# PX4FMUv1_7_1.net
KiCad netlist of a schematic drawn in EAGLE
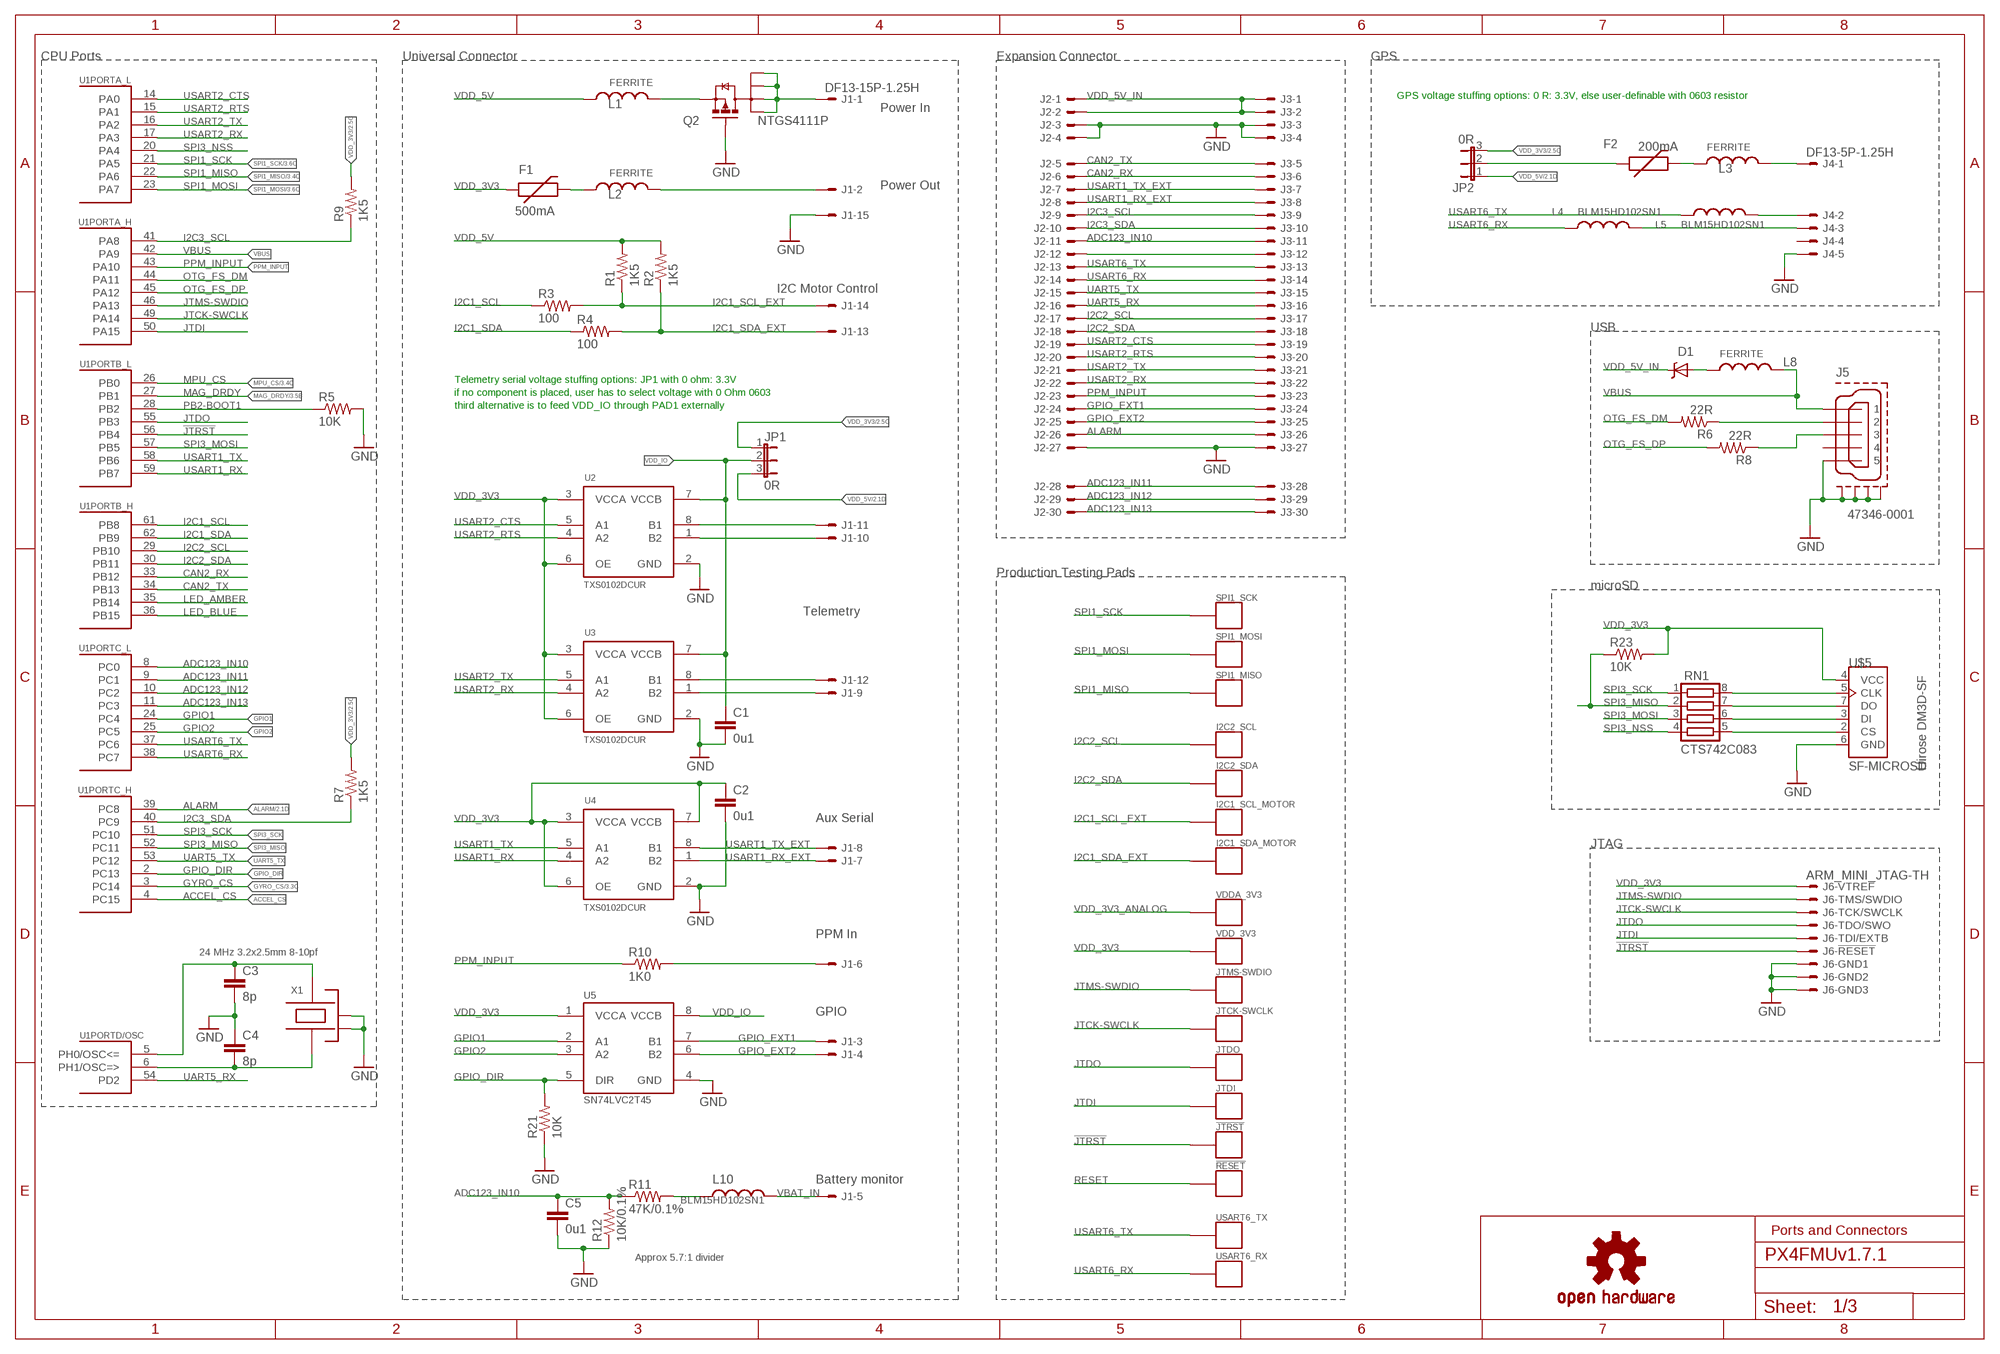
[diagram p0: schematic, sheet 1]
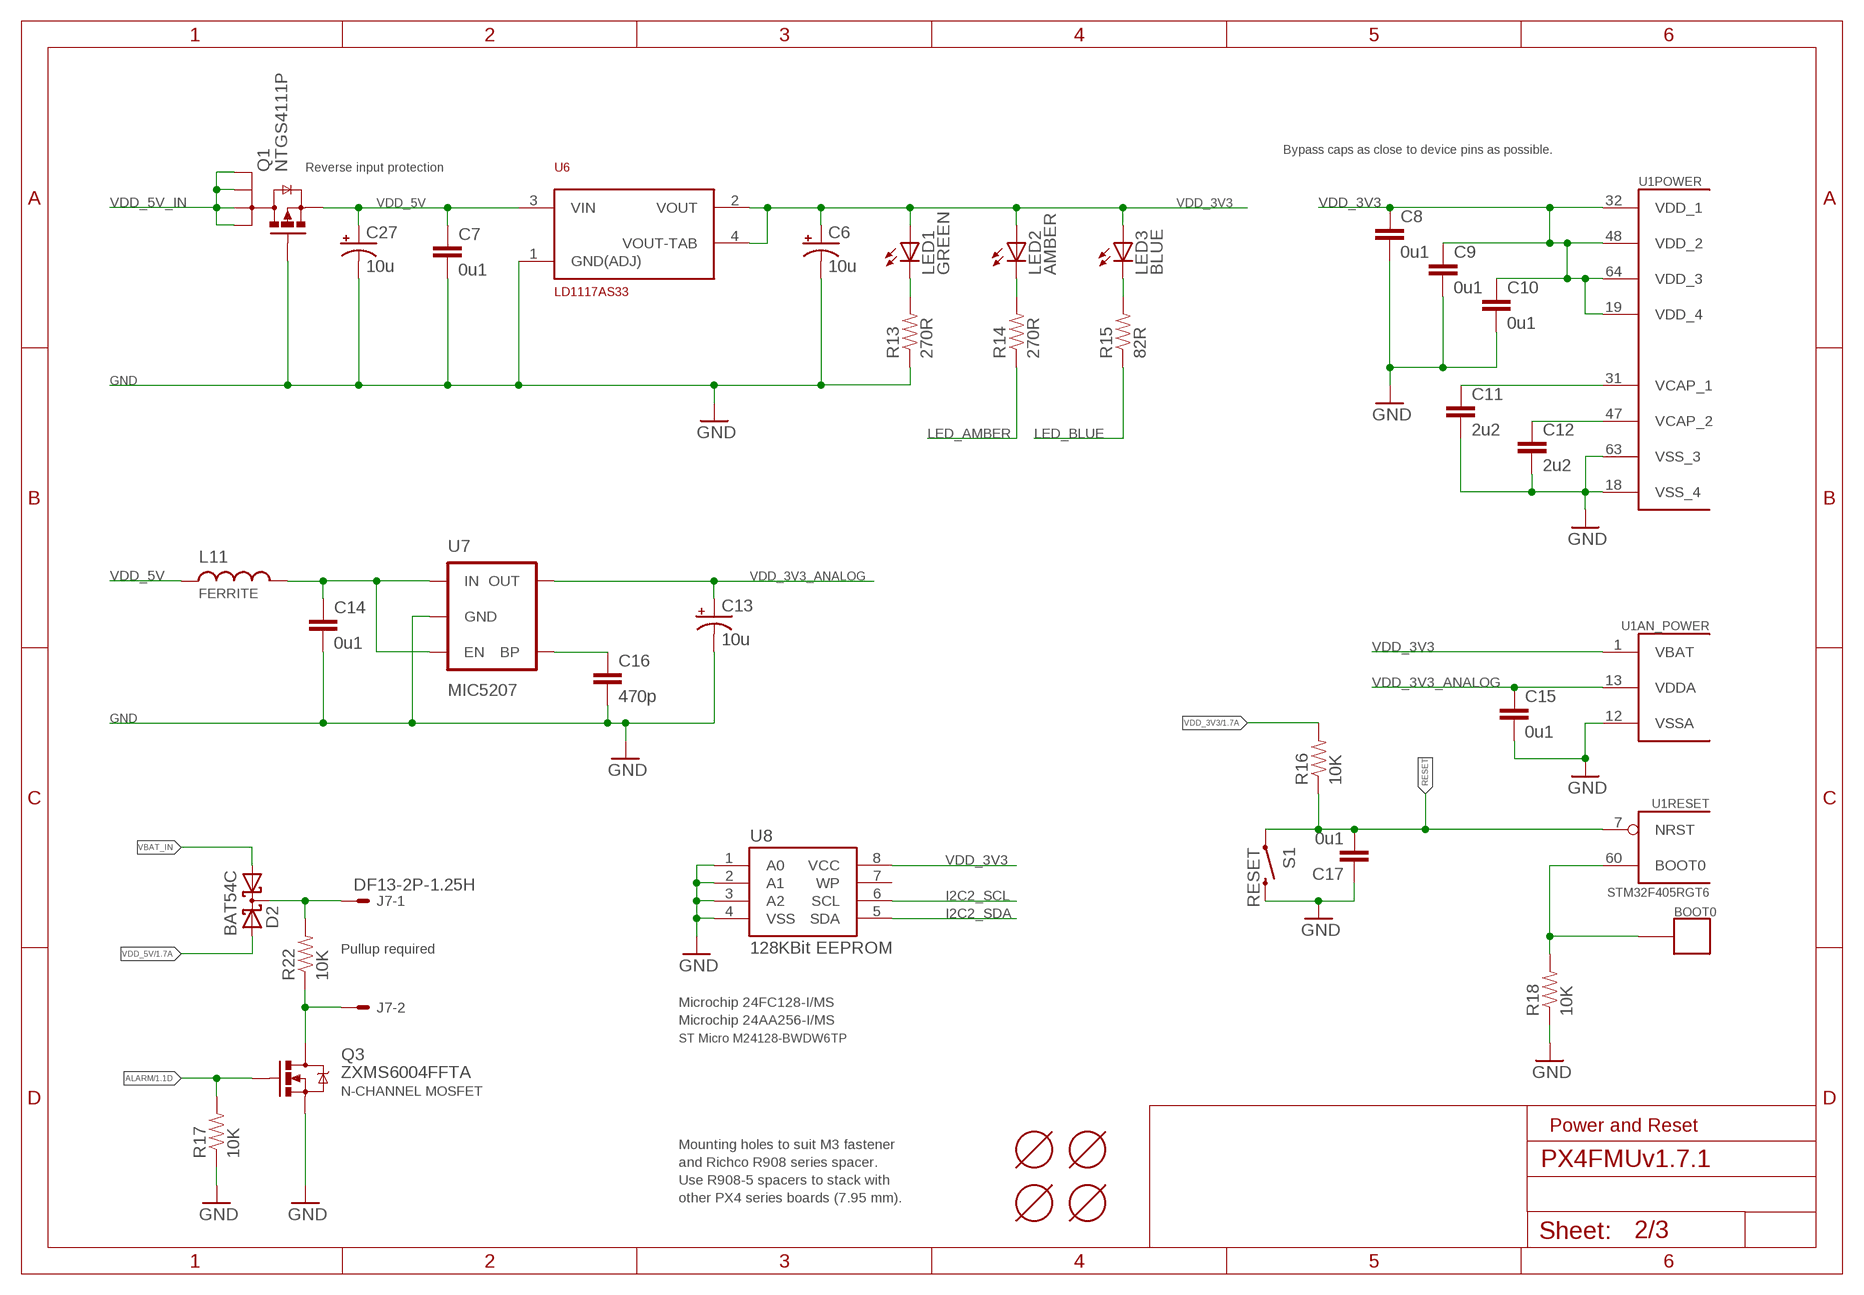
[diagram p1: schematic, sheet 2]
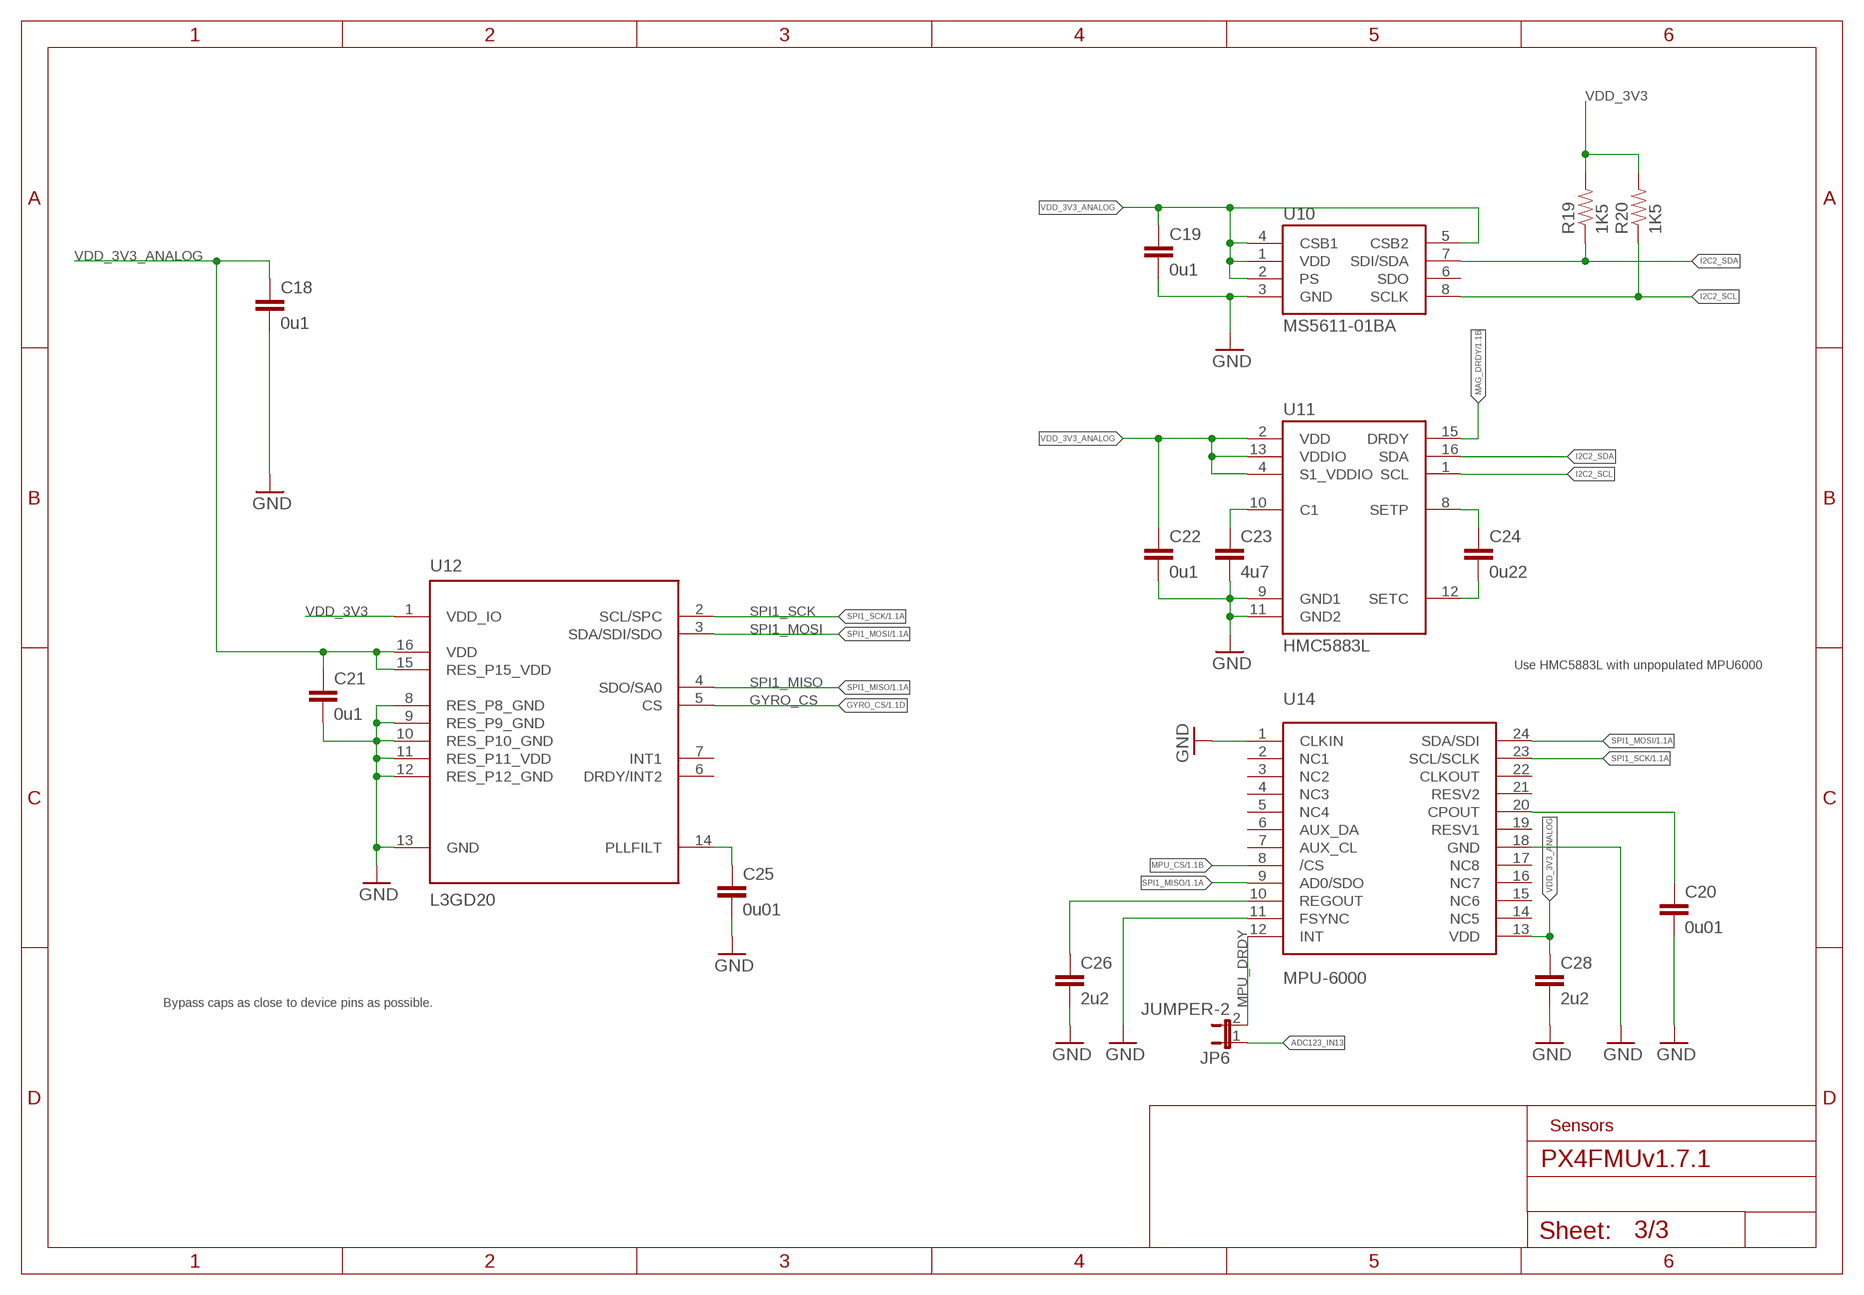
[diagram p2: schematic, sheet 3]

(export (version "E")
  (design (tool "Eeschema 10.0.6"))
  (components
    (comp (ref "BOOT0")
      (value "PAD.04")
      (footprint "eagle-import:PAD.04X.04")
      (libsource (lib "eagle-import") (part "PAD.04"))
    )
    (comp (ref "C6")
      (value "10u")
      (footprint "eagle-import:EIA3216")
      (fields (field (name "PARTNO") "F931A106MAA"))
      (libsource (lib "eagle-import") (part "CAP_POL1206"))
    )
    (comp (ref "C7")
      (value "0u1")
      (footprint "eagle-import:0402-CAP")
      (fields (field (name "PARTNO") "CC0402ZRY5V7BB104"))
      (libsource (lib "eagle-import") (part "CAP0402-CAP"))
    )
    (comp (ref "C8")
      (value "0u1")
      (footprint "eagle-import:0402-CAP")
      (fields (field (name "PARTNO") "CC0402ZRY5V7BB104"))
      (libsource (lib "eagle-import") (part "CAP0402-CAP"))
    )
    (comp (ref "C9")
      (value "0u1")
      (footprint "eagle-import:0402-CAP")
      (fields (field (name "PARTNO") "CC0402ZRY5V7BB104"))
      (libsource (lib "eagle-import") (part "CAP0402-CAP"))
    )
    (comp (ref "C10")
      (value "0u1")
      (footprint "eagle-import:0402-CAP")
      (fields (field (name "PARTNO") "CC0402ZRY5V7BB104"))
      (libsource (lib "eagle-import") (part "CAP0402-CAP"))
    )
    (comp (ref "C11")
      (value "2u2")
      (footprint "eagle-import:0402-CAP")
      (fields (field (name "PARTNO") "C1608Y5V1C225Z"))
      (libsource (lib "eagle-import") (part "CAP0402-CAP"))
    )
    (comp (ref "C12")
      (value "2u2")
      (footprint "eagle-import:0402-CAP")
      (fields (field (name "PARTNO") "C1608Y5V1C225Z"))
      (libsource (lib "eagle-import") (part "CAP0402-CAP"))
    )
    (comp (ref "C13")
      (value "10u")
      (footprint "eagle-import:EIA3216")
      (fields (field (name "PARTNO") "F931A106MAA"))
      (libsource (lib "eagle-import") (part "CAP_POL1206"))
    )
    (comp (ref "C14")
      (value "0u1")
      (footprint "eagle-import:0402-CAP")
      (fields (field (name "PARTNO") "CC0402ZRY5V7BB104"))
      (libsource (lib "eagle-import") (part "CAP0402-CAP"))
    )
    (comp (ref "C15")
      (value "0u1")
      (footprint "eagle-import:0402-CAP")
      (fields (field (name "PARTNO") "CC0402ZRY5V7BB104"))
      (libsource (lib "eagle-import") (part "CAP0402-CAP"))
    )
    (comp (ref "C16")
      (value "470p")
      (footprint "eagle-import:0402-CAP")
      (fields (field (name "PARTNO") "CC0402KRX7R9BB471"))
      (libsource (lib "eagle-import") (part "CAP0402-CAP"))
    )
    (comp (ref "C17")
      (value "0u1")
      (footprint "eagle-import:0402-CAP")
      (fields (field (name "PARTNO") "CC0402ZRY5V7BB104"))
      (libsource (lib "eagle-import") (part "CAP0402-CAP"))
    )
    (comp (ref "C27")
      (value "10u")
      (footprint "eagle-import:EIA3216")
      (fields (field (name "PARTNO") "F931A106MAA"))
      (libsource (lib "eagle-import") (part "CAP_POL1206"))
    )
    (comp (ref "D2")
      (value "BAT54C")
      (footprint "eagle-import:SOT23-3")
      (fields (field (name "PARTNO") "BAT54C-7-F"))
      (libsource (lib "eagle-import") (part "BAT54C"))
    )
    (comp (ref "J7")
      (value "DF13-2P-1.25H")
      (footprint "eagle-import:DF13A-2P-1.25H")
      (fields (field (name "PARTNO") "DF13-2P-1.25H(20)"))
      (libsource (lib "eagle-import") (part "DF13-2P-1.25?H"))
    )
    (comp (ref "L11")
      (value "FERRITE")
      (footprint "eagle-import:0402-IND")
      (fields (field (name "PARTNO") "BKP1005HS121-T"))
      (libsource (lib "eagle-import") (part "INDUCTOR0402"))
    )
    (comp (ref "LED1")
      (value "GREEN")
      (footprint "eagle-import:LED-0603")
      (fields (field (name "PARTNO") "LNJ337W83RA"))
      (libsource (lib "eagle-import") (part "LED0603"))
    )
    (comp (ref "LED2")
      (value "AMBER")
      (footprint "eagle-import:LED-0603")
      (fields (field (name "PARTNO") "LNJ437W84RA"))
      (libsource (lib "eagle-import") (part "LED0603"))
    )
    (comp (ref "LED3")
      (value "BLUE")
      (footprint "eagle-import:LED-0603")
      (fields (field (name "PARTNO") "LNJ937W8CRA"))
      (libsource (lib "eagle-import") (part "LED0603"))
    )
    (comp (ref "Q1")
      (value "NTGS4111P")
      (footprint "eagle-import:TSOP-6")
      (libsource (lib "eagle-import") (part "NTGS4111P"))
    )
    (comp (ref "Q3")
      (value "ZXMS6004FFTA")
      (footprint "eagle-import:SOT23-3")
      (libsource (lib "eagle-import") (part "MOSFET-NCHANNELSMD"))
    )
    (comp (ref "R13")
      (value "270R")
      (footprint "eagle-import:0402-RES")
      (fields (field (name "PARTNO") "RC0402JR-07270RL"))
      (libsource (lib "eagle-import") (part "RESISTOR0402-RES"))
    )
    (comp (ref "R14")
      (value "270R")
      (footprint "eagle-import:0402-RES")
      (fields (field (name "PARTNO") "RC0402JR-07270RL"))
      (libsource (lib "eagle-import") (part "RESISTOR0402-RES"))
    )
    (comp (ref "R15")
      (value "82R")
      (footprint "eagle-import:0402-RES")
      (fields (field (name "PARTNO") "RC0402JR-0782RL"))
      (libsource (lib "eagle-import") (part "RESISTOR0402-RES"))
    )
    (comp (ref "R16")
      (value "10K")
      (footprint "eagle-import:0402-RES")
      (fields (field (name "PARTNO") "RMCF0402FT10K0"))
      (libsource (lib "eagle-import") (part "RESISTOR0402-RES"))
    )
    (comp (ref "R17")
      (value "10K")
      (footprint "eagle-import:0402-RES")
      (fields (field (name "PARTNO") "RMCF0402FT10K0"))
      (libsource (lib "eagle-import") (part "RESISTOR0402-RES"))
    )
    (comp (ref "R18")
      (value "10K")
      (footprint "eagle-import:0402-RES")
      (fields (field (name "PARTNO") "RMCF0402FT10K0"))
      (libsource (lib "eagle-import") (part "RESISTOR0402-RES"))
    )
    (comp (ref "R22")
      (value "10K")
      (footprint "eagle-import:0402-RES")
      (fields (field (name "PARTNO") "RMCF0402FT10K0"))
      (libsource (lib "eagle-import") (part "RESISTOR0402-RES"))
    )
    (comp (ref "S1")
      (value "RESET")
      (footprint "eagle-import:EVQP7J01K")
      (fields (field (name "PARTNO") "EVQP7J01K"))
      (libsource (lib "eagle-import") (part "SWITCH-MOMENTARY-2"))
    )
    (comp (ref "U$1")
      (value "MOUNT-HOLE3.1MM")
      (footprint "eagle-import:MOUNT-HOLE3.1")
      (libsource (lib "eagle-import") (part "MOUNT-HOLE3.1MM"))
    )
    (comp (ref "U$2")
      (value "MOUNT-HOLE3.1MM")
      (footprint "eagle-import:MOUNT-HOLE3.1")
      (libsource (lib "eagle-import") (part "MOUNT-HOLE3.1MM"))
    )
    (comp (ref "U$3")
      (value "MOUNT-HOLE3.1MM")
      (footprint "eagle-import:MOUNT-HOLE3.1")
      (libsource (lib "eagle-import") (part "MOUNT-HOLE3.1MM"))
    )
    (comp (ref "U$4")
      (value "MOUNT-HOLE3.1MM")
      (footprint "eagle-import:MOUNT-HOLE3.1")
      (libsource (lib "eagle-import") (part "MOUNT-HOLE3.1MM"))
    )
    (comp (ref "U1")
      (value "STM32F405RGT6")
      (footprint "eagle-import:TQFP64")
      (fields (field (name "PARTNO") "STM32F405RGT6"))
      (libsource (lib "eagle-import") (part "STM32F20X_TQFP64"))
    )
    (comp (ref "U6")
      (value "LD1117AS33")
      (footprint "eagle-import:SOT-223")
      (libsource (lib "eagle-import") (part "LD1117AS33"))
    )
    (comp (ref "U7")
      (value "MIC5207")
      (footprint "eagle-import:SOT23-5")
      (fields (field (name "PARTNO") "MIC5207-3.3YM5"))
      (libsource (lib "eagle-import") (part "V_REG_LDOSMD"))
    )
    (comp (ref "U8")
      (value "128KBit EEPROM")
      (footprint "eagle-import:MSOP-8")
      (fields (field (name "PARTNO") "24FC128-I/MS"))
      (libsource (lib "eagle-import") (part "EEPROM-I2CMSOP"))
    )
    (comp (ref "C18")
      (value "0u1")
      (footprint "eagle-import:0402-CAP")
      (fields (field (name "PARTNO") "CC0402ZRY5V7BB104"))
      (libsource (lib "eagle-import") (part "CAP0402-CAP"))
    )
    (comp (ref "C19")
      (value "0u1")
      (footprint "eagle-import:0402-CAP")
      (fields (field (name "PARTNO") "CC0402ZRY5V7BB104"))
      (libsource (lib "eagle-import") (part "CAP0402-CAP"))
    )
    (comp (ref "C20")
      (value "0u01")
      (footprint "eagle-import:0402-CAP")
      (fields (field (name "PARTNO") "CC0402KRX7R7BB103"))
      (libsource (lib "eagle-import") (part "CAP0402-CAP"))
    )
    (comp (ref "C21")
      (value "0u1")
      (footprint "eagle-import:0402-CAP")
      (fields (field (name "PARTNO") "CC0402ZRY5V7BB104"))
      (libsource (lib "eagle-import") (part "CAP0402-CAP"))
    )
    (comp (ref "C22")
      (value "0u1")
      (footprint "eagle-import:0402-CAP")
      (fields (field (name "PARTNO") "CC0402ZRY5V7BB104"))
      (libsource (lib "eagle-import") (part "CAP0402-CAP"))
    )
    (comp (ref "C23")
      (value "4u7")
      (footprint "eagle-import:0402-CAP")
      (fields (field (name "PARTNO") "C1608Y5V0J475Z"))
      (libsource (lib "eagle-import") (part "CAP0402-CAP"))
    )
    (comp (ref "C24")
      (value "0u22")
      (footprint "eagle-import:0402-CAP")
      (fields (field (name "PARTNO") "C1005Y5V1C224Z"))
      (libsource (lib "eagle-import") (part "CAP0402-CAP"))
    )
    (comp (ref "C25")
      (value "0u01")
      (footprint "eagle-import:0402-CAP")
      (fields (field (name "PARTNO") "CC0402KRX7R7BB103"))
      (libsource (lib "eagle-import") (part "CAP0402-CAP"))
    )
    (comp (ref "C26")
      (value "2u2")
      (footprint "eagle-import:0402-CAP")
      (fields (field (name "PARTNO") "C1608Y5V1C225Z"))
      (libsource (lib "eagle-import") (part "CAP0402-CAP"))
    )
    (comp (ref "C28")
      (value "2u2")
      (footprint "eagle-import:0402-CAP")
      (fields (field (name "PARTNO") "C1608Y5V1C225Z"))
      (libsource (lib "eagle-import") (part "CAP0402-CAP"))
    )
    (comp (ref "JP6")
      (value "JUMPER-2")
      (footprint "eagle-import:SJ_2")
      (libsource (lib "eagle-import") (part "JUMPER-2"))
    )
    (comp (ref "R19")
      (value "1K5")
      (footprint "eagle-import:0402-RES")
      (fields (field (name "PARTNO") "RMCF0402JT1K50"))
      (libsource (lib "eagle-import") (part "RESISTOR0402-RES"))
    )
    (comp (ref "R20")
      (value "1K5")
      (footprint "eagle-import:0402-RES")
      (fields (field (name "PARTNO") "RMCF0402JT1K50"))
      (libsource (lib "eagle-import") (part "RESISTOR0402-RES"))
    )
    (comp (ref "U10")
      (value "MS5611-01BA")
      (footprint "eagle-import:MS5611-01BA")
      (libsource (lib "eagle-import") (part "MS5611-01BA"))
    )
    (comp (ref "U11")
      (value "HMC5883L")
      (footprint "eagle-import:HMC5883L-MAN")
      (libsource (lib "eagle-import") (part "HMC5883L"))
    )
    (comp (ref "U12")
      (value "L3GD20")
      (footprint "eagle-import:L3G4200DH-MAN")
      (libsource (lib "eagle-import") (part "L3G4200DH-LL"))
    )
    (comp (ref "U14")
      (value "MPU-6000")
      (footprint "eagle-import:QFN-24")
      (libsource (lib "eagle-import") (part "MPU-6000"))
    )
    (comp (ref "!JTRST")
      (value "PAD.04")
      (footprint "eagle-import:PAD.04X.04")
      (libsource (lib "eagle-import") (part "PAD.04"))
    )
    (comp (ref "!RESET")
      (value "PAD.04")
      (footprint "eagle-import:PAD.04X.04")
      (libsource (lib "eagle-import") (part "PAD.04"))
    )
    (comp (ref "C1")
      (value "0u1")
      (footprint "eagle-import:0402-CAP")
      (fields (field (name "PARTNO") "CC0402ZRY5V7BB104"))
      (libsource (lib "eagle-import") (part "CAP0402-CAP"))
    )
    (comp (ref "C2")
      (value "0u1")
      (footprint "eagle-import:0402-CAP")
      (fields (field (name "PARTNO") "CC0402ZRY5V7BB104"))
      (libsource (lib "eagle-import") (part "CAP0402-CAP"))
    )
    (comp (ref "C3")
      (value "8p")
      (footprint "eagle-import:0402-CAP")
      (fields (field (name "PARTNO") "C1005C0G1H080C"))
      (libsource (lib "eagle-import") (part "CAP0402-CAP"))
    )
    (comp (ref "C4")
      (value "8p")
      (footprint "eagle-import:0402-CAP")
      (fields (field (name "PARTNO") "C1005C0G1H080C"))
      (libsource (lib "eagle-import") (part "CAP0402-CAP"))
    )
    (comp (ref "C5")
      (value "0u1")
      (footprint "eagle-import:0402-CAP")
      (fields (field (name "PARTNO") "CC0402ZRY5V7BB104"))
      (libsource (lib "eagle-import") (part "CAP0402-CAP"))
    )
    (comp (ref "D1")
      (value "MSS1P4-M3")
      (footprint "eagle-import:MICROSMP")
      (fields (field (name "PARTNO") "MSS1P4-M3/89A"))
      (libsource (lib "eagle-import") (part "DIODE-SCHOTTKY_MSMP"))
    )
    (comp (ref "F1")
      (value "500mA")
      (footprint "eagle-import:0402-PTC")
      (fields (field (name "PARTNO") "MF-FSMF050X-2"))
      (libsource (lib "eagle-import") (part "PTC0402"))
    )
    (comp (ref "F2")
      (value "200mA")
      (footprint "eagle-import:0402-PTC")
      (fields (field (name "PARTNO") "MF-FSMF020X-2"))
      (libsource (lib "eagle-import") (part "PTC0402"))
    )
    (comp (ref "I2C1_SCL_MOTOR")
      (value "PAD.03")
      (footprint "eagle-import:PAD.03X.03")
      (libsource (lib "eagle-import") (part "PAD.03"))
    )
    (comp (ref "I2C1_SDA_MOTOR")
      (value "PAD.03")
      (footprint "eagle-import:PAD.03X.03")
      (libsource (lib "eagle-import") (part "PAD.03"))
    )
    (comp (ref "I2C2_SCL")
      (value "PAD.03")
      (footprint "eagle-import:PAD.03X.03")
      (libsource (lib "eagle-import") (part "PAD.03"))
    )
    (comp (ref "I2C2_SDA")
      (value "PAD.04")
      (footprint "eagle-import:PAD.04X.04")
      (libsource (lib "eagle-import") (part "PAD.04"))
    )
    (comp (ref "J1")
      (value "DF13-15P-1.25H")
      (footprint "eagle-import:DF13A-15P-1.25H")
      (fields (field (name "PARTNO") "DF13A-15P-1.25H(20)"))
      (libsource (lib "eagle-import") (part "DF13-15P-1.25?H"))
    )
    (comp (ref "J2")
      (value "HEADER_2X15-REV")
      (footprint "eagle-import:HEADER_2MM_2X15_REVERSE")
      (fields (field (name "BOM") "EXCLUDE") (field (name "PARTNO") "953230-2000-AR-PR"))
      (libsource (lib "eagle-import") (part "HEADER_2X15-REV"))
    )
    (comp (ref "J3")
      (value "HEADER_2X15")
      (footprint "eagle-import:HEADER_2MM_2X15")
      (fields (field (name "PARTNO") "953230-2000-AR-PR"))
      (libsource (lib "eagle-import") (part "HEADER_2X15-SMD"))
    )
    (comp (ref "J4")
      (value "DF13-5P-1.25H")
      (footprint "eagle-import:DF13A-5P-1.25H")
      (fields (field (name "PARTNO") "DF13A-5P-1.25H(20)"))
      (libsource (lib "eagle-import") (part "DF13-5P-1.25?H"))
    )
    (comp (ref "J5")
      (value "47346-0001")
      (footprint "eagle-import:MOLEX-47346-0001")
      (libsource (lib "eagle-import") (part "MOLEX-47346-0001"))
    )
    (comp (ref "J6")
      (value "ARM_MINI_JTAG-TH")
      (footprint "eagle-import:FTSH-105-01-XXX-DV")
      (fields (field (name "PARTNO") "M50-3900542"))
      (libsource (lib "eagle-import") (part "ARM_MINI_JTAG-TH"))
    )
    (comp (ref "JP1")
      (value "0R")
      (footprint "eagle-import:SJ_3_0603_PASTE1&2")
      (fields (field (name "PARTNO") "RMCF0402ZT0R00"))
      (libsource (lib "eagle-import") (part "JUMPER-30603"))
    )
    (comp (ref "JP2")
      (value "0R")
      (footprint "eagle-import:SJ_3_0603_PASTE1&2")
      (fields (field (name "PARTNO") "RMCF0402ZT0R00"))
      (libsource (lib "eagle-import") (part "JUMPER-30603"))
    )
    (comp (ref "JTCK-SWCLK")
      (value "PAD.04")
      (footprint "eagle-import:PAD.04X.04")
      (libsource (lib "eagle-import") (part "PAD.04"))
    )
    (comp (ref "JTDI")
      (value "PAD.04")
      (footprint "eagle-import:PAD.04X.04")
      (libsource (lib "eagle-import") (part "PAD.04"))
    )
    (comp (ref "JTDO")
      (value "PAD.04")
      (footprint "eagle-import:PAD.04X.04")
      (libsource (lib "eagle-import") (part "PAD.04"))
    )
    (comp (ref "JTMS-SWDIO")
      (value "PAD.04")
      (footprint "eagle-import:PAD.04X.04")
      (libsource (lib "eagle-import") (part "PAD.04"))
    )
    (comp (ref "L1")
      (value "FERRITE")
      (footprint "eagle-import:0402-IND")
      (fields (field (name "PARTNO") "BKP1005HS121-T"))
      (libsource (lib "eagle-import") (part "INDUCTOR0402"))
    )
    (comp (ref "L2")
      (value "FERRITE")
      (footprint "eagle-import:0402-IND")
      (fields (field (name "PARTNO") "BKP1005HS121-T"))
      (libsource (lib "eagle-import") (part "INDUCTOR0402"))
    )
    (comp (ref "L3")
      (value "FERRITE")
      (footprint "eagle-import:0402-IND")
      (fields (field (name "PARTNO") "BKP1005HS121-T"))
      (libsource (lib "eagle-import") (part "INDUCTOR0402"))
    )
    (comp (ref "L4")
      (value "BLM15HD102SN1")
      (footprint "eagle-import:0402-IND")
      (libsource (lib "eagle-import") (part "INDUCTOR0402"))
    )
    (comp (ref "L5")
      (value "BLM15HD102SN1")
      (footprint "eagle-import:0402-IND")
      (libsource (lib "eagle-import") (part "INDUCTOR0402"))
    )
    (comp (ref "L8")
      (value "FERRITE")
      (footprint "eagle-import:0402-IND")
      (fields (field (name "PARTNO") "BKP1005HS121-T"))
      (libsource (lib "eagle-import") (part "INDUCTOR0402"))
    )
    (comp (ref "L10")
      (value "BLM15HD102SN1")
      (footprint "eagle-import:0402-IND")
      (libsource (lib "eagle-import") (part "INDUCTOR0402"))
    )
    (comp (ref "Q2")
      (value "NTGS4111P")
      (footprint "eagle-import:TSOP-6")
      (libsource (lib "eagle-import") (part "NTGS4111P"))
    )
    (comp (ref "R1")
      (value "1K5")
      (footprint "eagle-import:0402-RES")
      (fields (field (name "PARTNO") "RMCF0402JT1K50"))
      (libsource (lib "eagle-import") (part "RESISTOR0402-RES"))
    )
    (comp (ref "R2")
      (value "1K5")
      (footprint "eagle-import:0402-RES")
      (fields (field (name "PARTNO") "RMCF0402JT1K50"))
      (libsource (lib "eagle-import") (part "RESISTOR0402-RES"))
    )
    (comp (ref "R3")
      (value "100")
      (footprint "eagle-import:0402-RES")
      (fields (field (name "PARTNO") "RMCF0402JT100R"))
      (libsource (lib "eagle-import") (part "RESISTOR0402-RES"))
    )
    (comp (ref "R4")
      (value "100")
      (footprint "eagle-import:0402-RES")
      (fields (field (name "PARTNO") "RMCF0402JT100R"))
      (libsource (lib "eagle-import") (part "RESISTOR0402-RES"))
    )
    (comp (ref "R5")
      (value "10K")
      (footprint "eagle-import:0402-RES")
      (fields (field (name "PARTNO") "RMCF0402FT10K0"))
      (libsource (lib "eagle-import") (part "RESISTOR0402-RES"))
    )
    (comp (ref "R6")
      (value "22R")
      (footprint "eagle-import:0402-RES")
      (fields (field (name "PARTNO") "RMCF0402JT22R0"))
      (libsource (lib "eagle-import") (part "RESISTOR0402-RES"))
    )
    (comp (ref "R7")
      (value "1K5")
      (footprint "eagle-import:0402-RES")
      (fields (field (name "PARTNO") "RMCF0402JT1K50"))
      (libsource (lib "eagle-import") (part "RESISTOR0402-RES"))
    )
    (comp (ref "R8")
      (value "22R")
      (footprint "eagle-import:0402-RES")
      (fields (field (name "PARTNO") "RMCF0402JT22R0"))
      (libsource (lib "eagle-import") (part "RESISTOR0402-RES"))
    )
    (comp (ref "R9")
      (value "1K5")
      (footprint "eagle-import:0402-RES")
      (fields (field (name "PARTNO") "RMCF0402JT1K50"))
      (libsource (lib "eagle-import") (part "RESISTOR0402-RES"))
    )
    (comp (ref "R10")
      (value "1K0")
      (footprint "eagle-import:0402-RES")
      (fields (field (name "PARTNO") "RMCF0402JT1K00"))
      (libsource (lib "eagle-import") (part "RESISTOR0402-RES"))
    )
    (comp (ref "R11")
      (value "47K/0.1%")
      (footprint "eagle-import:0402-RES")
      (fields (field (name "PARTNO") "ERA-2AEB473X"))
      (libsource (lib "eagle-import") (part "RESISTOR0402-RES"))
    )
    (comp (ref "R12")
      (value "10K/0.1%")
      (footprint "eagle-import:0402-RES")
      (fields (field (name "PARTNO") "ERA-2AEB103X"))
      (libsource (lib "eagle-import") (part "RESISTOR0402-RES"))
    )
    (comp (ref "R21")
      (value "10K")
      (footprint "eagle-import:0402-RES")
      (fields (field (name "PARTNO") "RMCF0402FT10K0"))
      (libsource (lib "eagle-import") (part "RESISTOR0402-RES"))
    )
    (comp (ref "R23")
      (value "10K")
      (footprint "eagle-import:0402-RES")
      (fields (field (name "PARTNO") "RMCF0402FT10K0"))
      (libsource (lib "eagle-import") (part "RESISTOR0402-RES"))
    )
    (comp (ref "RN1")
      (value "CTS742C083")
      (footprint "eagle-import:CTS742C083")
      (fields (field (name "PARTNO") "TC164-JR-07100RL"))
      (libsource (lib "eagle-import") (part "CTS742C083"))
    )
    (comp (ref "SPI1_MISO")
      (value "PAD.04")
      (footprint "eagle-import:PAD.04X.04")
      (libsource (lib "eagle-import") (part "PAD.04"))
    )
    (comp (ref "SPI1_MOSI")
      (value "PAD.04")
      (footprint "eagle-import:PAD.04X.04")
      (libsource (lib "eagle-import") (part "PAD.04"))
    )
    (comp (ref "SPI1_SCK")
      (value "PAD.04")
      (footprint "eagle-import:PAD.04X.04")
      (libsource (lib "eagle-import") (part "PAD.04"))
    )
    (comp (ref "U$5")
      (value "SF-MICROSD")
      (footprint "eagle-import:MICROSD")
      (libsource (lib "eagle-import") (part "SF-MICROSD"))
    )
    (comp (ref "U$7")
      (value "OSHW-LOGOS")
      (footprint "eagle-import:OSHW-LOGO-S")
      (libsource (lib "eagle-import") (part "OSHW-LOGOS"))
    )
    (comp (ref "U2")
      (value "TXS0102DCUR")
      (footprint "eagle-import:TI-DCU")
      (libsource (lib "eagle-import") (part "TXS0102DCUR"))
    )
    (comp (ref "U3")
      (value "TXS0102DCUR")
      (footprint "eagle-import:TI-DCU")
      (libsource (lib "eagle-import") (part "TXS0102DCUR"))
    )
    (comp (ref "U4")
      (value "TXS0102DCUR")
      (footprint "eagle-import:TI-DCU")
      (libsource (lib "eagle-import") (part "TXS0102DCUR"))
    )
    (comp (ref "U5")
      (value "SN74LVC2T45")
      (footprint "eagle-import:TI-DCU")
      (libsource (lib "eagle-import") (part "SN74LVC2T45DCUR"))
    )
    (comp (ref "USART6_RX")
      (value "PAD.04")
      (footprint "eagle-import:PAD.04X.04")
      (libsource (lib "eagle-import") (part "PAD.04"))
    )
    (comp (ref "USART6_TX")
      (value "PAD.04")
      (footprint "eagle-import:PAD.04X.04")
      (libsource (lib "eagle-import") (part "PAD.04"))
    )
    (comp (ref "VDDA_3V3")
      (value "PAD.04")
      (footprint "eagle-import:PAD.04X.04")
      (libsource (lib "eagle-import") (part "PAD.04"))
    )
    (comp (ref "VDD_3V3")
      (value "PAD.04")
      (footprint "eagle-import:PAD.04X.04")
      (libsource (lib "eagle-import") (part "PAD.04"))
    )
    (comp (ref "X1")
      (value "24 MHz 3.2x2.5mm 8-10pf")
      (footprint "eagle-import:OSCILLATOR-3.2X2.5")
      (fields (field (name "PARTNO") "NX3225SA-24.000000MHZ"))
      (libsource (lib "eagle-import") (part "OSCILLATOR-3.2X2.5"))
    )
  )
  (nets
    (net (code "1") (name "ACCEL_CS") (class "Default")
      (node (ref "U1") (pin "4") (pinfunction "PC15_4") (pintype "bidirectional"))
    )
    (net (code "2") (name "ADC123_IN10") (class "Default")
      (node (ref "C5") (pin "1") (pinfunction "1_1") (pintype "passive"))
      (node (ref "J2") (pin "11") (pinfunction "S_11") (pintype "passive"))
      (node (ref "J3") (pin "11") (pinfunction "S_11") (pintype "passive"))
      (node (ref "R11") (pin "1") (pinfunction "1_1") (pintype "passive"))
      (node (ref "R12") (pin "2") (pinfunction "2_2") (pintype "passive"))
      (node (ref "U1") (pin "8") (pinfunction "PC0_8") (pintype "bidirectional"))
    )
    (net (code "3") (name "ADC123_IN11") (class "Default")
      (node (ref "J2") (pin "28") (pinfunction "S_28") (pintype "passive"))
      (node (ref "J3") (pin "28") (pinfunction "S_28") (pintype "passive"))
      (node (ref "U1") (pin "9") (pinfunction "PC1_9") (pintype "bidirectional"))
    )
    (net (code "4") (name "ADC123_IN12") (class "Default")
      (node (ref "J2") (pin "29") (pinfunction "S_29") (pintype "passive"))
      (node (ref "J3") (pin "29") (pinfunction "S_29") (pintype "passive"))
      (node (ref "U1") (pin "10") (pinfunction "PC2_10") (pintype "bidirectional"))
    )
    (net (code "5") (name "ADC123_IN13") (class "Default")
      (node (ref "J2") (pin "30") (pinfunction "S_30") (pintype "passive"))
      (node (ref "J3") (pin "30") (pinfunction "S_30") (pintype "passive"))
      (node (ref "JP6") (pin "1") (pinfunction "1_1") (pintype "passive"))
      (node (ref "U1") (pin "11") (pinfunction "PC3_11") (pintype "bidirectional"))
    )
    (net (code "6") (name "ALARM") (class "Default")
      (node (ref "J2") (pin "26") (pinfunction "S_26") (pintype "passive"))
      (node (ref "J3") (pin "26") (pinfunction "S_26") (pintype "passive"))
      (node (ref "Q3") (pin "1") (pinfunction "G_1") (pintype "passive"))
      (node (ref "R17") (pin "2") (pinfunction "2_2") (pintype "passive"))
      (node (ref "U1") (pin "39") (pinfunction "PC8_39") (pintype "bidirectional"))
    )
    (net (code "7") (name "CAN2_RX") (class "Default")
      (node (ref "J2") (pin "6") (pinfunction "S_6") (pintype "passive"))
      (node (ref "J3") (pin "6") (pinfunction "S_6") (pintype "passive"))
      (node (ref "U1") (pin "33") (pinfunction "PB12_33") (pintype "bidirectional"))
    )
    (net (code "8") (name "CAN2_TX") (class "Default")
      (node (ref "J2") (pin "5") (pinfunction "S_5") (pintype "passive"))
      (node (ref "J3") (pin "5") (pinfunction "S_5") (pintype "passive"))
      (node (ref "U1") (pin "34") (pinfunction "PB13_34") (pintype "bidirectional"))
    )
    (net (code "9") (name "GND") (class "Default")
      (node (ref "C1") (pin "2") (pinfunction "2_2") (pintype "passive"))
      (node (ref "C10") (pin "2") (pinfunction "2_2") (pintype "passive"))
      (node (ref "C11") (pin "2") (pinfunction "2_2") (pintype "passive"))
      (node (ref "C12") (pin "2") (pinfunction "2_2") (pintype "passive"))
      (node (ref "C13") (pin "C") (pinfunction "-_C") (pintype "passive"))
      (node (ref "C14") (pin "2") (pinfunction "2_2") (pintype "passive"))
      (node (ref "C15") (pin "2") (pinfunction "2_2") (pintype "passive"))
      (node (ref "C16") (pin "2") (pinfunction "2_2") (pintype "passive"))
      (node (ref "C17") (pin "1") (pinfunction "1_1") (pintype "passive"))
      (node (ref "C18") (pin "2") (pinfunction "2_2") (pintype "passive"))
      (node (ref "C19") (pin "2") (pinfunction "2_2") (pintype "passive"))
      (node (ref "C2") (pin "2") (pinfunction "2_2") (pintype "passive"))
      (node (ref "C20") (pin "2") (pinfunction "2_2") (pintype "passive"))
      (node (ref "C21") (pin "2") (pinfunction "2_2") (pintype "passive"))
      (node (ref "C22") (pin "2") (pinfunction "2_2") (pintype "passive"))
      (node (ref "C23") (pin "2") (pinfunction "2_2") (pintype "passive"))
      (node (ref "C25") (pin "2") (pinfunction "2_2") (pintype "passive"))
      (node (ref "C26") (pin "2") (pinfunction "2_2") (pintype "passive"))
      (node (ref "C27") (pin "C") (pinfunction "-_C") (pintype "passive"))
      (node (ref "C28") (pin "2") (pinfunction "2_2") (pintype "passive"))
      (node (ref "C3") (pin "2") (pinfunction "2_2") (pintype "passive"))
      (node (ref "C4") (pin "1") (pinfunction "1_1") (pintype "passive"))
      (node (ref "C5") (pin "2") (pinfunction "2_2") (pintype "passive"))
      (node (ref "C6") (pin "C") (pinfunction "-_C") (pintype "passive"))
      (node (ref "C7") (pin "2") (pinfunction "2_2") (pintype "passive"))
      (node (ref "C8") (pin "2") (pinfunction "2_2") (pintype "passive"))
      (node (ref "C9") (pin "2") (pinfunction "2_2") (pintype "passive"))
      (node (ref "J1") (pin "15") (pinfunction "S_15") (pintype "passive"))
      (node (ref "J2") (pin "27") (pinfunction "S_27") (pintype "passive"))
      (node (ref "J2") (pin "3") (pinfunction "S_3") (pintype "passive"))
      (node (ref "J2") (pin "4") (pinfunction "S_4") (pintype "passive"))
      (node (ref "J3") (pin "27") (pinfunction "S_27") (pintype "passive"))
      (node (ref "J3") (pin "3") (pinfunction "S_3") (pintype "passive"))
      (node (ref "J3") (pin "4") (pinfunction "S_4") (pintype "passive"))
      (node (ref "J4") (pin "5") (pinfunction "S_5") (pintype "passive"))
      (node (ref "J5") (pin "GND") (pinfunction "5_GND") (pintype "power_in"))
      (node (ref "J5") (pin "GND1") (pinfunction "GND1_GND1") (pintype "bidirectional"))
      (node (ref "J5") (pin "GND2") (pinfunction "GND2_GND2") (pintype "bidirectional"))
      (node (ref "J5") (pin "GND3") (pinfunction "GND3_GND3") (pintype "bidirectional"))
      (node (ref "J5") (pin "GND4") (pinfunction "GND4_GND4") (pintype "bidirectional"))
      (node (ref "J6") (pin "3") (pinfunction "S_3") (pintype "passive"))
      (node (ref "J6") (pin "5") (pinfunction "S_5") (pintype "passive"))
      (node (ref "J6") (pin "9") (pinfunction "S_9") (pintype "passive"))
      (node (ref "Q1") (pin "3") (pinfunction "G_3") (pintype "passive"))
      (node (ref "Q2") (pin "3") (pinfunction "G_3") (pintype "passive"))
      (node (ref "Q3") (pin "2") (pinfunction "S_2") (pintype "passive"))
      (node (ref "R12") (pin "1") (pinfunction "1_1") (pintype "passive"))
      (node (ref "R13") (pin "1") (pinfunction "1_1") (pintype "passive"))
      (node (ref "R17") (pin "1") (pinfunction "1_1") (pintype "passive"))
      (node (ref "R18") (pin "1") (pinfunction "1_1") (pintype "passive"))
      (node (ref "R21") (pin "1") (pinfunction "1_1") (pintype "passive"))
      (node (ref "R5") (pin "2") (pinfunction "2_2") (pintype "passive"))
      (node (ref "S1") (pin "B3") (pinfunction "2_B3") (pintype "passive"))
      (node (ref "U$5") (pin "6") (pinfunction "GND_6") (pintype "power_in"))
      (node (ref "U1") (pin "12") (pinfunction "VSSA_12") (pintype "power_in"))
      (node (ref "U1") (pin "18") (pinfunction "VSS_4_18") (pintype "power_in"))
      (node (ref "U1") (pin "63") (pinfunction "VSS_3_63") (pintype "power_in"))
      (node (ref "U10") (pin "3") (pinfunction "GND_3") (pintype "bidirectional"))
      (node (ref "U11") (pin "11") (pinfunction "GND2_11") (pintype "bidirectional"))
      (node (ref "U11") (pin "9") (pinfunction "GND1_9") (pintype "bidirectional"))
      (node (ref "U12") (pin "10") (pinfunction "RES_P10_GND_10") (pintype "bidirectional"))
      (node (ref "U12") (pin "11") (pinfunction "RES_P11_VDD_11") (pintype "bidirectional"))
      (node (ref "U12") (pin "12") (pinfunction "RES_P12_GND_12") (pintype "bidirectional"))
      (node (ref "U12") (pin "13") (pinfunction "GND_13") (pintype "bidirectional"))
      (node (ref "U12") (pin "8") (pinfunction "RES_P8_GND_8") (pintype "bidirectional"))
      (node (ref "U12") (pin "9") (pinfunction "RES_P9_GND_9") (pintype "bidirectional"))
      (node (ref "U14") (pin "1") (pinfunction "CLKIN_1") (pintype "bidirectional"))
      (node (ref "U14") (pin "11") (pinfunction "FSYNC_11") (pintype "bidirectional"))
      (node (ref "U14") (pin "18") (pinfunction "GND_18") (pintype "bidirectional"))
      (node (ref "U2") (pin "2") (pinfunction "GND_2") (pintype "power_in"))
      (node (ref "U3") (pin "2") (pinfunction "GND_2") (pintype "power_in"))
      (node (ref "U4") (pin "2") (pinfunction "GND_2") (pintype "power_in"))
      (node (ref "U5") (pin "4") (pinfunction "GND_4") (pintype "power_in"))
      (node (ref "U6") (pin "1") (pinfunction "GND(ADJ)_1") (pintype "bidirectional"))
      (node (ref "U7") (pin "2") (pinfunction "GND_2") (pintype "input"))
      (node (ref "U8") (pin "1") (pinfunction "A0_1") (pintype "bidirectional"))
      (node (ref "U8") (pin "2") (pinfunction "A1_2") (pintype "bidirectional"))
      (node (ref "U8") (pin "3") (pinfunction "A2_3") (pintype "bidirectional"))
      (node (ref "U8") (pin "4") (pinfunction "VSS_4") (pintype "power_in"))
      (node (ref "X1") (pin "2") (pinfunction "NC_2_2") (pintype "power_in"))
      (node (ref "X1") (pin "4") (pinfunction "NC_4_4") (pintype "power_in"))
    )
    (net (code "10") (name "GPIO1") (class "Default")
      (node (ref "U1") (pin "24") (pinfunction "PC4_24") (pintype "bidirectional"))
      (node (ref "U5") (pin "2") (pinfunction "A1_2") (pintype "bidirectional"))
    )
    (net (code "11") (name "GPIO2") (class "Default")
      (node (ref "U1") (pin "25") (pinfunction "PC5_25") (pintype "bidirectional"))
      (node (ref "U5") (pin "3") (pinfunction "A2_3") (pintype "bidirectional"))
    )
    (net (code "12") (name "GPIO_DIR") (class "Default")
      (node (ref "R21") (pin "2") (pinfunction "2_2") (pintype "passive"))
      (node (ref "U1") (pin "2") (pinfunction "PC13_2") (pintype "bidirectional"))
      (node (ref "U5") (pin "5") (pinfunction "DIR_5") (pintype "input"))
    )
    (net (code "13") (name "GPIO_EXT1") (class "Default")
      (node (ref "J1") (pin "3") (pinfunction "S_3") (pintype "passive"))
      (node (ref "J2") (pin "24") (pinfunction "S_24") (pintype "passive"))
      (node (ref "J3") (pin "24") (pinfunction "S_24") (pintype "passive"))
      (node (ref "U5") (pin "7") (pinfunction "B1_7") (pintype "bidirectional"))
    )
    (net (code "14") (name "GPIO_EXT2") (class "Default")
      (node (ref "J1") (pin "4") (pinfunction "S_4") (pintype "passive"))
      (node (ref "J2") (pin "25") (pinfunction "S_25") (pintype "passive"))
      (node (ref "J3") (pin "25") (pinfunction "S_25") (pintype "passive"))
      (node (ref "U5") (pin "6") (pinfunction "B2_6") (pintype "bidirectional"))
    )
    (net (code "15") (name "GYRO_CS") (class "Default")
      (node (ref "U1") (pin "3") (pinfunction "PC14_3") (pintype "bidirectional"))
      (node (ref "U12") (pin "5") (pinfunction "CS_5") (pintype "input"))
    )
    (net (code "16") (name "I2C1_SCL") (class "Default")
      (node (ref "R3") (pin "1") (pinfunction "1_1") (pintype "passive"))
      (node (ref "U1") (pin "61") (pinfunction "PB8_61") (pintype "bidirectional"))
    )
    (net (code "17") (name "I2C1_SCL_EXT") (class "Default")
      (node (ref "I2C1_SCL_MOTOR") (pin "P$1") (pinfunction "P$1_P$1") (pintype "passive"))
      (node (ref "J1") (pin "14") (pinfunction "S_14") (pintype "passive"))
      (node (ref "R1") (pin "1") (pinfunction "1_1") (pintype "passive"))
      (node (ref "R3") (pin "2") (pinfunction "2_2") (pintype "passive"))
    )
    (net (code "18") (name "I2C1_SDA") (class "Default")
      (node (ref "R4") (pin "1") (pinfunction "1_1") (pintype "passive"))
      (node (ref "U1") (pin "62") (pinfunction "PB9_62") (pintype "bidirectional"))
    )
    (net (code "19") (name "I2C1_SDA_EXT") (class "Default")
      (node (ref "I2C1_SDA_MOTOR") (pin "P$1") (pinfunction "P$1_P$1") (pintype "passive"))
      (node (ref "J1") (pin "13") (pinfunction "S_13") (pintype "passive"))
      (node (ref "R2") (pin "1") (pinfunction "1_1") (pintype "passive"))
      (node (ref "R4") (pin "2") (pinfunction "2_2") (pintype "passive"))
    )
    (net (code "20") (name "I2C2_SCL") (class "Default")
      (node (ref "I2C2_SCL") (pin "P$1") (pinfunction "P$1_P$1") (pintype "passive"))
      (node (ref "J2") (pin "17") (pinfunction "S_17") (pintype "passive"))
      (node (ref "J3") (pin "17") (pinfunction "S_17") (pintype "passive"))
      (node (ref "R20") (pin "1") (pinfunction "1_1") (pintype "passive"))
      (node (ref "U1") (pin "29") (pinfunction "PB10_29") (pintype "bidirectional"))
      (node (ref "U10") (pin "8") (pinfunction "SCLK_8") (pintype "bidirectional"))
      (node (ref "U11") (pin "1") (pinfunction "SCL_1") (pintype "bidirectional"))
      (node (ref "U8") (pin "6") (pinfunction "SCL_6") (pintype "bidirectional"))
    )
    (net (code "21") (name "I2C2_SDA") (class "Default")
      (node (ref "I2C2_SDA") (pin "P$1") (pinfunction "P$1_P$1") (pintype "passive"))
      (node (ref "J2") (pin "18") (pinfunction "S_18") (pintype "passive"))
      (node (ref "J3") (pin "18") (pinfunction "S_18") (pintype "passive"))
      (node (ref "R19") (pin "1") (pinfunction "1_1") (pintype "passive"))
      (node (ref "U1") (pin "30") (pinfunction "PB11_30") (pintype "bidirectional"))
      (node (ref "U10") (pin "7") (pinfunction "SDI/SDA_7") (pintype "bidirectional"))
      (node (ref "U11") (pin "16") (pinfunction "SDA_16") (pintype "bidirectional"))
      (node (ref "U8") (pin "5") (pinfunction "SDA_5") (pintype "bidirectional"))
    )
    (net (code "22") (name "I2C3_SCL") (class "Default")
      (node (ref "J2") (pin "9") (pinfunction "S_9") (pintype "passive"))
      (node (ref "J3") (pin "9") (pinfunction "S_9") (pintype "passive"))
      (node (ref "R9") (pin "1") (pinfunction "1_1") (pintype "passive"))
      (node (ref "U1") (pin "41") (pinfunction "PA8_41") (pintype "bidirectional"))
    )
    (net (code "23") (name "I2C3_SDA") (class "Default")
      (node (ref "J2") (pin "10") (pinfunction "S_10") (pintype "passive"))
      (node (ref "J3") (pin "10") (pinfunction "S_10") (pintype "passive"))
      (node (ref "R7") (pin "1") (pinfunction "1_1") (pintype "passive"))
      (node (ref "U1") (pin "40") (pinfunction "PC9_40") (pintype "bidirectional"))
    )
    (net (code "24") (name "JTCK-SWCLK") (class "Default")
      (node (ref "J6") (pin "4") (pinfunction "S_4") (pintype "passive"))
      (node (ref "JTCK-SWCLK") (pin "P$1") (pinfunction "P$1_P$1") (pintype "passive"))
      (node (ref "U1") (pin "49") (pinfunction "PA14_49") (pintype "bidirectional"))
    )
    (net (code "25") (name "JTDI") (class "Default")
      (node (ref "J6") (pin "8") (pinfunction "S_8") (pintype "passive"))
      (node (ref "JTDI") (pin "P$1") (pinfunction "P$1_P$1") (pintype "passive"))
      (node (ref "U1") (pin "50") (pinfunction "PA15_50") (pintype "bidirectional"))
    )
    (net (code "26") (name "JTDO") (class "Default")
      (node (ref "J6") (pin "6") (pinfunction "S_6") (pintype "passive"))
      (node (ref "JTDO") (pin "P$1") (pinfunction "P$1_P$1") (pintype "passive"))
      (node (ref "U1") (pin "55") (pinfunction "PB3_55") (pintype "bidirectional"))
    )
    (net (code "27") (name "JTMS-SWDIO") (class "Default")
      (node (ref "J6") (pin "2") (pinfunction "S_2") (pintype "passive"))
      (node (ref "JTMS-SWDIO") (pin "P$1") (pinfunction "P$1_P$1") (pintype "passive"))
      (node (ref "U1") (pin "46") (pinfunction "PA13_46") (pintype "bidirectional"))
    )
    (net (code "28") (name "LED_AMBER") (class "Default")
      (node (ref "R14") (pin "1") (pinfunction "1_1") (pintype "passive"))
      (node (ref "U1") (pin "35") (pinfunction "PB14_35") (pintype "bidirectional"))
    )
    (net (code "29") (name "LED_BLUE") (class "Default")
      (node (ref "R15") (pin "1") (pinfunction "1_1") (pintype "passive"))
      (node (ref "U1") (pin "36") (pinfunction "PB15_36") (pintype "bidirectional"))
    )
    (net (code "30") (name "MAG_DRDY") (class "Default")
      (node (ref "U1") (pin "27") (pinfunction "PB1_27") (pintype "bidirectional"))
      (node (ref "U11") (pin "15") (pinfunction "DRDY_15") (pintype "bidirectional"))
    )
    (net (code "31") (name "MPU_CS") (class "Default")
      (node (ref "U1") (pin "26") (pinfunction "PB0_26") (pintype "bidirectional"))
      (node (ref "U14") (pin "8") (pinfunction "/CS_8") (pintype "bidirectional"))
    )
    (net (code "32") (name "Net-(D1-A)") (class "Default")
      (node (ref "D1") (pin "ANODE") (pinfunction "A_ANODE") (pintype "passive"))
      (node (ref "L8") (pin "1") (pinfunction "1_1") (pintype "passive"))
    )
    (net (code "33") (name "Net-(D2-CC)") (class "Default")
      (node (ref "D2") (pin "3") (pinfunction "CC_3") (pintype "passive"))
      (node (ref "J7") (pin "1") (pinfunction "S_1") (pintype "passive"))
      (node (ref "R22") (pin "2") (pinfunction "2_2") (pintype "passive"))
    )
    (net (code "34") (name "Net-(F1-Pad2)") (class "Default")
      (node (ref "F1") (pin "2") (pinfunction "2_2") (pintype "bidirectional"))
      (node (ref "L2") (pin "1") (pinfunction "1_1") (pintype "passive"))
    )
    (net (code "35") (name "Net-(F2-Pad1)") (class "Default")
      (node (ref "F2") (pin "1") (pinfunction "1_1") (pintype "bidirectional"))
      (node (ref "JP2") (pin "2") (pinfunction "2_2") (pintype "passive"))
    )
    (net (code "36") (name "Net-(F2-Pad2)") (class "Default")
      (node (ref "F2") (pin "2") (pinfunction "2_2") (pintype "bidirectional"))
      (node (ref "L3") (pin "1") (pinfunction "1_1") (pintype "passive"))
    )
    (net (code "37") (name "Net-(J1A-S)") (class "Default")
      (node (ref "J1") (pin "1") (pinfunction "S_1") (pintype "passive"))
      (node (ref "Q2") (pin "1") (pinfunction "D_1") (pintype "passive"))
      (node (ref "Q2") (pin "2") (pinfunction "D1_2") (pintype "passive"))
      (node (ref "Q2") (pin "5") (pinfunction "D2_5") (pintype "passive"))
      (node (ref "Q2") (pin "6") (pinfunction "D3_6") (pintype "passive"))
    )
    (net (code "38") (name "Net-(J1B-S)") (class "Default")
      (node (ref "J1") (pin "10") (pinfunction "S_10") (pintype "passive"))
      (node (ref "U2") (pin "1") (pinfunction "B2_1") (pintype "bidirectional"))
    )
    (net (code "39") (name "Net-(J1C-S)") (class "Default")
      (node (ref "J1") (pin "11") (pinfunction "S_11") (pintype "passive"))
      (node (ref "U2") (pin "8") (pinfunction "B1_8") (pintype "bidirectional"))
    )
    (net (code "40") (name "Net-(J1D-S)") (class "Default")
      (node (ref "J1") (pin "12") (pinfunction "S_12") (pintype "passive"))
      (node (ref "U3") (pin "8") (pinfunction "B1_8") (pintype "bidirectional"))
    )
    (net (code "41") (name "Net-(J1H-S)") (class "Default")
      (node (ref "J1") (pin "2") (pinfunction "S_2") (pintype "passive"))
      (node (ref "L2") (pin "2") (pinfunction "2_2") (pintype "passive"))
    )
    (net (code "42") (name "Net-(J1L-S)") (class "Default")
      (node (ref "J1") (pin "6") (pinfunction "S_6") (pintype "passive"))
      (node (ref "R10") (pin "2") (pinfunction "2_2") (pintype "passive"))
    )
    (net (code "43") (name "Net-(J1O-S)") (class "Default")
      (node (ref "J1") (pin "9") (pinfunction "S_9") (pintype "passive"))
      (node (ref "U3") (pin "1") (pinfunction "B2_1") (pintype "bidirectional"))
    )
    (net (code "44") (name "Net-(J2D-S)") (class "Default")
      (node (ref "J2") (pin "12") (pinfunction "S_12") (pintype "passive"))
      (node (ref "J3") (pin "12") (pinfunction "S_12") (pintype "passive"))
    )
    (net (code "45") (name "Net-(J4A-S)") (class "Default")
      (node (ref "J4") (pin "1") (pinfunction "S_1") (pintype "passive"))
      (node (ref "L3") (pin "2") (pinfunction "2_2") (pintype "passive"))
    )
    (net (code "46") (name "Net-(J4B-S)") (class "Default")
      (node (ref "J4") (pin "2") (pinfunction "S_2") (pintype "passive"))
      (node (ref "L5") (pin "2") (pinfunction "2_2") (pintype "passive"))
    )
    (net (code "47") (name "Net-(J4C-S)") (class "Default")
      (node (ref "J4") (pin "3") (pinfunction "S_3") (pintype "passive"))
      (node (ref "L4") (pin "2") (pinfunction "2_2") (pintype "passive"))
    )
    (net (code "48") (name "Net-(J5-2)") (class "Default")
      (node (ref "J5") (pin "D-") (pinfunction "2_D-") (pintype "bidirectional"))
      (node (ref "R6") (pin "1") (pinfunction "1_1") (pintype "passive"))
    )
    (net (code "49") (name "Net-(J5-3)") (class "Default")
      (node (ref "J5") (pin "D+") (pinfunction "3_D+") (pintype "bidirectional"))
      (node (ref "R8") (pin "1") (pinfunction "1_1") (pintype "passive"))
    )
    (net (code "50") (name "Net-(J7B-S)") (class "Default")
      (node (ref "J7") (pin "2") (pinfunction "S_2") (pintype "passive"))
      (node (ref "Q3") (pin "3") (pinfunction "D_3") (pintype "passive"))
      (node (ref "R22") (pin "1") (pinfunction "1_1") (pintype "passive"))
    )
    (net (code "51") (name "Net-(L10-Pad1)") (class "Default")
      (node (ref "L10") (pin "1") (pinfunction "1_1") (pintype "passive"))
      (node (ref "R11") (pin "2") (pinfunction "2_2") (pintype "passive"))
    )
    (net (code "52") (name "Net-(LED1-PadC)") (class "Default")
      (node (ref "LED1") (pin "C") (pinfunction "C_C") (pintype "passive"))
      (node (ref "R13") (pin "2") (pinfunction "2_2") (pintype "passive"))
    )
    (net (code "53") (name "Net-(LED2-PadC)") (class "Default")
      (node (ref "LED2") (pin "C") (pinfunction "C_C") (pintype "passive"))
      (node (ref "R14") (pin "2") (pinfunction "2_2") (pintype "passive"))
    )
    (net (code "54") (name "Net-(LED3-PadC)") (class "Default")
      (node (ref "LED3") (pin "C") (pinfunction "C_C") (pintype "passive"))
      (node (ref "R15") (pin "2") (pinfunction "2_2") (pintype "passive"))
    )
    (net (code "55") (name "Net-(Q2-S)") (class "Default")
      (node (ref "L1") (pin "2") (pinfunction "2_2") (pintype "passive"))
      (node (ref "Q2") (pin "4") (pinfunction "S_4") (pintype "passive"))
    )
    (net (code "56") (name "Net-(U$5-CLK)") (class "Default")
      (node (ref "RN1") (pin "8") (pinfunction "8_8") (pintype "passive"))
      (node (ref "U$5") (pin "5") (pinfunction "CLK_5") (pintype "bidirectional"))
    )
    (net (code "57") (name "Net-(U$5-CS)") (class "Default")
      (node (ref "RN1") (pin "5") (pinfunction "5_5") (pintype "passive"))
      (node (ref "U$5") (pin "2") (pinfunction "CS_2") (pintype "bidirectional"))
    )
    (net (code "58") (name "Net-(U$5-DI)") (class "Default")
      (node (ref "RN1") (pin "6") (pinfunction "6_6") (pintype "passive"))
      (node (ref "U$5") (pin "3") (pinfunction "DI_3") (pintype "bidirectional"))
    )
    (net (code "59") (name "Net-(U$5-DO)") (class "Default")
      (node (ref "RN1") (pin "7") (pinfunction "7_7") (pintype "passive"))
      (node (ref "U$5") (pin "7") (pinfunction "DO_7") (pintype "bidirectional"))
    )
    (net (code "60") (name "Net-(U1H-PH0{slash}OSC<=)") (class "Default")
      (node (ref "C3") (pin "1") (pinfunction "1_1") (pintype "passive"))
      (node (ref "U1") (pin "5") (pinfunction "PH0/OSC<=_5") (pintype "bidirectional"))
      (node (ref "X1") (pin "3") (pinfunction "3_3") (pintype "bidirectional"))
    )
    (net (code "61") (name "Net-(U1H-PH1{slash}OSC=>)") (class "Default")
      (node (ref "C4") (pin "2") (pinfunction "2_2") (pintype "passive"))
      (node (ref "U1") (pin "6") (pinfunction "PH1/OSC=>_6") (pintype "bidirectional"))
      (node (ref "X1") (pin "1") (pinfunction "1_1") (pintype "bidirectional"))
    )
    (net (code "62") (name "Net-(U1I-VCAP_1)") (class "Default")
      (node (ref "C11") (pin "1") (pinfunction "1_1") (pintype "passive"))
      (node (ref "U1") (pin "31") (pinfunction "VCAP_1_31") (pintype "power_in"))
    )
    (net (code "63") (name "Net-(U1I-VCAP_2)") (class "Default")
      (node (ref "C12") (pin "1") (pinfunction "1_1") (pintype "passive"))
      (node (ref "U1") (pin "47") (pinfunction "VCAP_2_47") (pintype "power_in"))
    )
    (net (code "64") (name "Net-(U1J-BOOT0)") (class "Default")
      (node (ref "BOOT0") (pin "P$1") (pinfunction "P$1_P$1") (pintype "passive"))
      (node (ref "R18") (pin "2") (pinfunction "2_2") (pintype "passive"))
      (node (ref "U1") (pin "60") (pinfunction "BOOT0_60") (pintype "input"))
    )
    (net (code "65") (name "Net-(U7-BP)") (class "Default")
      (node (ref "C16") (pin "1") (pinfunction "1_1") (pintype "passive"))
      (node (ref "U7") (pin "4") (pinfunction "BP_4") (pintype "input"))
    )
    (net (code "66") (name "Net-(U7-EN)") (class "Default")
      (node (ref "C14") (pin "1") (pinfunction "1_1") (pintype "passive"))
      (node (ref "L11") (pin "2") (pinfunction "2_2") (pintype "passive"))
      (node (ref "U7") (pin "1") (pinfunction "IN_1") (pintype "input"))
      (node (ref "U7") (pin "3") (pinfunction "EN_3") (pintype "input"))
    )
    (net (code "67") (name "Net-(U11-C1)") (class "Default")
      (node (ref "C23") (pin "1") (pinfunction "1_1") (pintype "passive"))
      (node (ref "U11") (pin "10") (pinfunction "C1_10") (pintype "bidirectional"))
    )
    (net (code "68") (name "Net-(U11-SETC)") (class "Default")
      (node (ref "C24") (pin "2") (pinfunction "2_2") (pintype "passive"))
      (node (ref "U11") (pin "12") (pinfunction "SETC_12") (pintype "bidirectional"))
    )
    (net (code "69") (name "Net-(U11-SETP)") (class "Default")
      (node (ref "C24") (pin "1") (pinfunction "1_1") (pintype "passive"))
      (node (ref "U11") (pin "8") (pinfunction "SETP_8") (pintype "bidirectional"))
    )
    (net (code "70") (name "Net-(U12-PLLFILT)") (class "Default")
      (node (ref "C25") (pin "1") (pinfunction "1_1") (pintype "passive"))
      (node (ref "U12") (pin "14") (pinfunction "PLLFILT_14") (pintype "bidirectional"))
    )
    (net (code "71") (name "Net-(U14-CPOUT)") (class "Default")
      (node (ref "C20") (pin "1") (pinfunction "1_1") (pintype "passive"))
      (node (ref "U14") (pin "20") (pinfunction "CPOUT_20") (pintype "bidirectional"))
    )
    (net (code "72") (name "Net-(U14-INT)") (class "Default")
      (node (ref "JP6") (pin "2") (pinfunction "2_2") (pintype "passive"))
      (node (ref "U14") (pin "12") (pinfunction "INT_12") (pintype "bidirectional"))
    )
    (net (code "73") (name "Net-(U14-REGOUT)") (class "Default")
      (node (ref "C26") (pin "1") (pinfunction "1_1") (pintype "passive"))
      (node (ref "U14") (pin "10") (pinfunction "REGOUT_10") (pintype "bidirectional"))
    )
    (net (code "74") (name "OTG_FS_DM") (class "Default")
      (node (ref "R6") (pin "2") (pinfunction "2_2") (pintype "passive"))
      (node (ref "U1") (pin "44") (pinfunction "PA11_44") (pintype "bidirectional"))
    )
    (net (code "75") (name "OTG_FS_DP") (class "Default")
      (node (ref "R8") (pin "2") (pinfunction "2_2") (pintype "passive"))
      (node (ref "U1") (pin "45") (pinfunction "PA12_45") (pintype "bidirectional"))
    )
    (net (code "76") (name "PB2-BOOT1") (class "Default")
      (node (ref "R5") (pin "1") (pinfunction "1_1") (pintype "passive"))
      (node (ref "U1") (pin "28") (pinfunction "PB2_28") (pintype "bidirectional"))
    )
    (net (code "77") (name "PPM_INPUT") (class "Default")
      (node (ref "J2") (pin "23") (pinfunction "S_23") (pintype "passive"))
      (node (ref "J3") (pin "23") (pinfunction "S_23") (pintype "passive"))
      (node (ref "R10") (pin "1") (pinfunction "1_1") (pintype "passive"))
      (node (ref "U1") (pin "43") (pinfunction "PA10_43") (pintype "bidirectional"))
    )
    (net (code "78") (name "RESET") (class "Default")
      (node (ref "!RESET") (pin "P$1") (pinfunction "P$1_P$1") (pintype "passive"))
      (node (ref "C17") (pin "2") (pinfunction "2_2") (pintype "passive"))
      (node (ref "R16") (pin "1") (pinfunction "1_1") (pintype "passive"))
      (node (ref "S1") (pin "A1") (pinfunction "1_A1") (pintype "passive"))
      (node (ref "U1") (pin "7") (pinfunction "NRST_7") (pintype "input"))
    )
    (net (code "79") (name "SPI1_MISO") (class "Default")
      (node (ref "SPI1_MISO") (pin "P$1") (pinfunction "P$1_P$1") (pintype "passive"))
      (node (ref "U1") (pin "22") (pinfunction "PA6_22") (pintype "bidirectional"))
      (node (ref "U12") (pin "4") (pinfunction "SDO/SA0_4") (pintype "bidirectional"))
      (node (ref "U14") (pin "9") (pinfunction "AD0/SDO_9") (pintype "bidirectional"))
    )
    (net (code "80") (name "SPI1_MOSI") (class "Default")
      (node (ref "SPI1_MOSI") (pin "P$1") (pinfunction "P$1_P$1") (pintype "passive"))
      (node (ref "U1") (pin "23") (pinfunction "PA7_23") (pintype "bidirectional"))
      (node (ref "U12") (pin "3") (pinfunction "SDA/SDI/SDO_3") (pintype "bidirectional"))
      (node (ref "U14") (pin "24") (pinfunction "SDA/SDI_24") (pintype "bidirectional"))
    )
    (net (code "81") (name "SPI1_SCK") (class "Default")
      (node (ref "SPI1_SCK") (pin "P$1") (pinfunction "P$1_P$1") (pintype "passive"))
      (node (ref "U1") (pin "21") (pinfunction "PA5_21") (pintype "bidirectional"))
      (node (ref "U12") (pin "2") (pinfunction "SCL/SPC_2") (pintype "input"))
      (node (ref "U14") (pin "23") (pinfunction "SCL/SCLK_23") (pintype "bidirectional"))
    )
    (net (code "82") (name "SPI3_MISO") (class "Default")
      (node (ref "R23") (pin "1") (pinfunction "1_1") (pintype "passive"))
      (node (ref "RN1") (pin "2") (pinfunction "2_2") (pintype "passive"))
      (node (ref "U1") (pin "52") (pinfunction "PC11_52") (pintype "bidirectional"))
    )
    (net (code "83") (name "SPI3_MOSI") (class "Default")
      (node (ref "RN1") (pin "3") (pinfunction "3_3") (pintype "passive"))
      (node (ref "U1") (pin "57") (pinfunction "PB5_57") (pintype "bidirectional"))
    )
    (net (code "84") (name "SPI3_NSS") (class "Default")
      (node (ref "RN1") (pin "4") (pinfunction "4_4") (pintype "passive"))
      (node (ref "U1") (pin "20") (pinfunction "PA4_20") (pintype "bidirectional"))
    )
    (net (code "85") (name "SPI3_SCK") (class "Default")
      (node (ref "RN1") (pin "1") (pinfunction "1_1") (pintype "passive"))
      (node (ref "U1") (pin "51") (pinfunction "PC10_51") (pintype "bidirectional"))
    )
    (net (code "86") (name "UART5_RX") (class "Default")
      (node (ref "J2") (pin "16") (pinfunction "S_16") (pintype "passive"))
      (node (ref "J3") (pin "16") (pinfunction "S_16") (pintype "passive"))
      (node (ref "U1") (pin "54") (pinfunction "PD2_54") (pintype "bidirectional"))
    )
    (net (code "87") (name "UART5_TX") (class "Default")
      (node (ref "J2") (pin "15") (pinfunction "S_15") (pintype "passive"))
      (node (ref "J3") (pin "15") (pinfunction "S_15") (pintype "passive"))
      (node (ref "U1") (pin "53") (pinfunction "PC12_53") (pintype "bidirectional"))
    )
    (net (code "88") (name "USART1_RX") (class "Default")
      (node (ref "U1") (pin "59") (pinfunction "PB7_59") (pintype "bidirectional"))
      (node (ref "U4") (pin "4") (pinfunction "A2_4") (pintype "bidirectional"))
    )
    (net (code "89") (name "USART1_RX_EXT") (class "Default")
      (node (ref "J1") (pin "7") (pinfunction "S_7") (pintype "passive"))
      (node (ref "J2") (pin "8") (pinfunction "S_8") (pintype "passive"))
      (node (ref "J3") (pin "8") (pinfunction "S_8") (pintype "passive"))
      (node (ref "U4") (pin "1") (pinfunction "B2_1") (pintype "bidirectional"))
    )
    (net (code "90") (name "USART1_TX") (class "Default")
      (node (ref "U1") (pin "58") (pinfunction "PB6_58") (pintype "bidirectional"))
      (node (ref "U4") (pin "5") (pinfunction "A1_5") (pintype "bidirectional"))
    )
    (net (code "91") (name "USART1_TX_EXT") (class "Default")
      (node (ref "J1") (pin "8") (pinfunction "S_8") (pintype "passive"))
      (node (ref "J2") (pin "7") (pinfunction "S_7") (pintype "passive"))
      (node (ref "J3") (pin "7") (pinfunction "S_7") (pintype "passive"))
      (node (ref "U4") (pin "8") (pinfunction "B1_8") (pintype "bidirectional"))
    )
    (net (code "92") (name "USART2_CTS") (class "Default")
      (node (ref "J2") (pin "19") (pinfunction "S_19") (pintype "passive"))
      (node (ref "J3") (pin "19") (pinfunction "S_19") (pintype "passive"))
      (node (ref "U1") (pin "14") (pinfunction "PA0_14") (pintype "bidirectional"))
      (node (ref "U2") (pin "5") (pinfunction "A1_5") (pintype "bidirectional"))
    )
    (net (code "93") (name "USART2_RTS") (class "Default")
      (node (ref "J2") (pin "20") (pinfunction "S_20") (pintype "passive"))
      (node (ref "J3") (pin "20") (pinfunction "S_20") (pintype "passive"))
      (node (ref "U1") (pin "15") (pinfunction "PA1_15") (pintype "bidirectional"))
      (node (ref "U2") (pin "4") (pinfunction "A2_4") (pintype "bidirectional"))
    )
    (net (code "94") (name "USART2_RX") (class "Default")
      (node (ref "J2") (pin "22") (pinfunction "S_22") (pintype "passive"))
      (node (ref "J3") (pin "22") (pinfunction "S_22") (pintype "passive"))
      (node (ref "U1") (pin "17") (pinfunction "PA3_17") (pintype "bidirectional"))
      (node (ref "U3") (pin "4") (pinfunction "A2_4") (pintype "bidirectional"))
    )
    (net (code "95") (name "USART2_TX") (class "Default")
      (node (ref "J2") (pin "21") (pinfunction "S_21") (pintype "passive"))
      (node (ref "J3") (pin "21") (pinfunction "S_21") (pintype "passive"))
      (node (ref "U1") (pin "16") (pinfunction "PA2_16") (pintype "bidirectional"))
      (node (ref "U3") (pin "5") (pinfunction "A1_5") (pintype "bidirectional"))
    )
    (net (code "96") (name "USART6_RX") (class "Default")
      (node (ref "J2") (pin "14") (pinfunction "S_14") (pintype "passive"))
      (node (ref "J3") (pin "14") (pinfunction "S_14") (pintype "passive"))
      (node (ref "L4") (pin "1") (pinfunction "1_1") (pintype "passive"))
      (node (ref "U1") (pin "38") (pinfunction "PC7_38") (pintype "bidirectional"))
      (node (ref "USART6_RX") (pin "P$1") (pinfunction "P$1_P$1") (pintype "passive"))
    )
    (net (code "97") (name "USART6_TX") (class "Default")
      (node (ref "J2") (pin "13") (pinfunction "S_13") (pintype "passive"))
      (node (ref "J3") (pin "13") (pinfunction "S_13") (pintype "passive"))
      (node (ref "L5") (pin "1") (pinfunction "1_1") (pintype "passive"))
      (node (ref "U1") (pin "37") (pinfunction "PC6_37") (pintype "bidirectional"))
      (node (ref "USART6_TX") (pin "P$1") (pinfunction "P$1_P$1") (pintype "passive"))
    )
    (net (code "98") (name "VBAT_IN") (class "Default")
      (node (ref "D2") (pin "1") (pinfunction "A1_1") (pintype "passive"))
      (node (ref "J1") (pin "5") (pinfunction "S_5") (pintype "passive"))
      (node (ref "L10") (pin "2") (pinfunction "2_2") (pintype "passive"))
    )
    (net (code "99") (name "VBUS") (class "Default")
      (node (ref "J5") (pin "VBUS") (pinfunction "1_VBUS") (pintype "power_in"))
      (node (ref "L8") (pin "2") (pinfunction "2_2") (pintype "passive"))
      (node (ref "U1") (pin "42") (pinfunction "PA9_42") (pintype "bidirectional"))
    )
    (net (code "100") (name "VDD_3V3") (class "Default")
      (node (ref "C10") (pin "1") (pinfunction "1_1") (pintype "passive"))
      (node (ref "C2") (pin "1") (pinfunction "1_1") (pintype "passive"))
      (node (ref "C6") (pin "A") (pinfunction "+_A") (pintype "passive"))
      (node (ref "C8") (pin "1") (pinfunction "1_1") (pintype "passive"))
      (node (ref "C9") (pin "1") (pinfunction "1_1") (pintype "passive"))
      (node (ref "F1") (pin "1") (pinfunction "1_1") (pintype "bidirectional"))
      (node (ref "J6") (pin "1") (pinfunction "S_1") (pintype "passive"))
      (node (ref "JP1") (pin "1") (pinfunction "1_1") (pintype "passive"))
      (node (ref "JP2") (pin "3") (pinfunction "3_3") (pintype "passive"))
      (node (ref "LED1") (pin "A") (pinfunction "A_A") (pintype "passive"))
      (node (ref "LED2") (pin "A") (pinfunction "A_A") (pintype "passive"))
      (node (ref "LED3") (pin "A") (pinfunction "A_A") (pintype "passive"))
      (node (ref "R16") (pin "2") (pinfunction "2_2") (pintype "passive"))
      (node (ref "R19") (pin "2") (pinfunction "2_2") (pintype "passive"))
      (node (ref "R20") (pin "2") (pinfunction "2_2") (pintype "passive"))
      (node (ref "R23") (pin "2") (pinfunction "2_2") (pintype "passive"))
      (node (ref "R7") (pin "2") (pinfunction "2_2") (pintype "passive"))
      (node (ref "R9") (pin "2") (pinfunction "2_2") (pintype "passive"))
      (node (ref "U$5") (pin "4") (pinfunction "VCC_4") (pintype "passive"))
      (node (ref "U1") (pin "1") (pinfunction "VBAT_1") (pintype "power_in"))
      (node (ref "U1") (pin "19") (pinfunction "VDD_4_19") (pintype "power_in"))
      (node (ref "U1") (pin "32") (pinfunction "VDD_1_32") (pintype "power_in"))
      (node (ref "U1") (pin "48") (pinfunction "VDD_2_48") (pintype "power_in"))
      (node (ref "U1") (pin "64") (pinfunction "VDD_3_64") (pintype "power_in"))
      (node (ref "U12") (pin "1") (pinfunction "VDD_IO_1") (pintype "bidirectional"))
      (node (ref "U2") (pin "3") (pinfunction "VCCA_3") (pintype "input"))
      (node (ref "U2") (pin "6") (pinfunction "OE_6") (pintype "input"))
      (node (ref "U3") (pin "3") (pinfunction "VCCA_3") (pintype "input"))
      (node (ref "U3") (pin "6") (pinfunction "OE_6") (pintype "input"))
      (node (ref "U4") (pin "3") (pinfunction "VCCA_3") (pintype "input"))
      (node (ref "U4") (pin "6") (pinfunction "OE_6") (pintype "input"))
      (node (ref "U4") (pin "7") (pinfunction "VCCB_7") (pintype "input"))
      (node (ref "U5") (pin "1") (pinfunction "VCCA_1") (pintype "passive"))
      (node (ref "U6") (pin "2") (pinfunction "VOUT_2") (pintype "bidirectional"))
      (node (ref "U6") (pin "4") (pinfunction "VOUT-TAB_4") (pintype "bidirectional"))
      (node (ref "U8") (pin "8") (pinfunction "VCC_8") (pintype "power_in"))
      (node (ref "VDD_3V3") (pin "P$1") (pinfunction "P$1_P$1") (pintype "passive"))
    )
    (net (code "101") (name "VDD_3V3_ANALOG") (class "Default")
      (node (ref "C13") (pin "A") (pinfunction "+_A") (pintype "passive"))
      (node (ref "C15") (pin "1") (pinfunction "1_1") (pintype "passive"))
      (node (ref "C18") (pin "1") (pinfunction "1_1") (pintype "passive"))
      (node (ref "C19") (pin "1") (pinfunction "1_1") (pintype "passive"))
      (node (ref "C21") (pin "1") (pinfunction "1_1") (pintype "passive"))
      (node (ref "C22") (pin "1") (pinfunction "1_1") (pintype "passive"))
      (node (ref "C28") (pin "1") (pinfunction "1_1") (pintype "passive"))
      (node (ref "U1") (pin "13") (pinfunction "VDDA_13") (pintype "power_in"))
      (node (ref "U10") (pin "1") (pinfunction "VDD_1") (pintype "bidirectional"))
      (node (ref "U10") (pin "2") (pinfunction "PS_2") (pintype "bidirectional"))
      (node (ref "U10") (pin "4") (pinfunction "CSB1_4") (pintype "bidirectional"))
      (node (ref "U10") (pin "5") (pinfunction "CSB2_5") (pintype "bidirectional"))
      (node (ref "U11") (pin "13") (pinfunction "VDDIO_13") (pintype "bidirectional"))
      (node (ref "U11") (pin "2") (pinfunction "VDD_2") (pintype "bidirectional"))
      (node (ref "U11") (pin "4") (pinfunction "S1_VDDIO_4") (pintype "bidirectional"))
      (node (ref "U12") (pin "15") (pinfunction "RES_P15_VDD_15") (pintype "bidirectional"))
      (node (ref "U12") (pin "16") (pinfunction "VDD_16") (pintype "bidirectional"))
      (node (ref "U14") (pin "13") (pinfunction "VDD_13") (pintype "bidirectional"))
      (node (ref "U7") (pin "5") (pinfunction "OUT_5") (pintype "passive"))
      (node (ref "VDDA_3V3") (pin "P$1") (pinfunction "P$1_P$1") (pintype "passive"))
    )
    (net (code "102") (name "VDD_5V") (class "Default")
      (node (ref "C27") (pin "A") (pinfunction "+_A") (pintype "passive"))
      (node (ref "C7") (pin "1") (pinfunction "1_1") (pintype "passive"))
      (node (ref "D2") (pin "2") (pinfunction "A2_2") (pintype "passive"))
      (node (ref "JP1") (pin "3") (pinfunction "3_3") (pintype "passive"))
      (node (ref "JP2") (pin "1") (pinfunction "1_1") (pintype "passive"))
      (node (ref "L1") (pin "1") (pinfunction "1_1") (pintype "passive"))
      (node (ref "L11") (pin "1") (pinfunction "1_1") (pintype "passive"))
      (node (ref "Q1") (pin "4") (pinfunction "S_4") (pintype "passive"))
      (node (ref "R1") (pin "2") (pinfunction "2_2") (pintype "passive"))
      (node (ref "R2") (pin "2") (pinfunction "2_2") (pintype "passive"))
      (node (ref "U6") (pin "3") (pinfunction "VIN_3") (pintype "bidirectional"))
    )
    (net (code "103") (name "VDD_5V_IN") (class "Default")
      (node (ref "D1") (pin "CATHODE") (pinfunction "C_CATHODE") (pintype "passive"))
      (node (ref "J2") (pin "1") (pinfunction "S_1") (pintype "passive"))
      (node (ref "J2") (pin "2") (pinfunction "S_2") (pintype "passive"))
      (node (ref "J3") (pin "1") (pinfunction "S_1") (pintype "passive"))
      (node (ref "J3") (pin "2") (pinfunction "S_2") (pintype "passive"))
      (node (ref "Q1") (pin "1") (pinfunction "D_1") (pintype "passive"))
      (node (ref "Q1") (pin "2") (pinfunction "D1_2") (pintype "passive"))
      (node (ref "Q1") (pin "5") (pinfunction "D2_5") (pintype "passive"))
      (node (ref "Q1") (pin "6") (pinfunction "D3_6") (pintype "passive"))
    )
    (net (code "104") (name "VDD_IO") (class "Default")
      (node (ref "C1") (pin "1") (pinfunction "1_1") (pintype "passive"))
      (node (ref "JP1") (pin "2") (pinfunction "2_2") (pintype "passive"))
      (node (ref "U2") (pin "7") (pinfunction "VCCB_7") (pintype "input"))
      (node (ref "U3") (pin "7") (pinfunction "VCCB_7") (pintype "input"))
      (node (ref "U5") (pin "8") (pinfunction "VCCB_8") (pintype "passive"))
    )
    (net (code "105") (name "unconnected-(J4D-S-Pad4)") (class "Default")
      (node (ref "J4") (pin "4") (pinfunction "S_4") (pintype "passive"))
    )
    (net (code "106") (name "unconnected-(J5-4-PadID)") (class "Default")
      (node (ref "J5") (pin "ID") (pinfunction "4_ID") (pintype "passive"))
    )
    (net (code "107") (name "unconnected-(U8-WP-Pad7)") (class "Default")
      (node (ref "U8") (pin "7") (pinfunction "WP_7") (pintype "bidirectional"))
    )
    (net (code "108") (name "unconnected-(U10-SDO-Pad6)") (class "Default")
      (node (ref "U10") (pin "6") (pinfunction "SDO_6") (pintype "bidirectional"))
    )
    (net (code "109") (name "unconnected-(U11-NC_P3-Pad3)") (class "Default")
      (node (ref "U11") (pin "3") (pinfunction "NC_P3_3") (pintype "no_connect"))
    )
    (net (code "110") (name "unconnected-(U11-NC_P5-Pad5)") (class "Default")
      (node (ref "U11") (pin "5") (pinfunction "NC_P5_5") (pintype "no_connect"))
    )
    (net (code "111") (name "unconnected-(U11-NC_P6-Pad6)") (class "Default")
      (node (ref "U11") (pin "6") (pinfunction "NC_P6_6") (pintype "no_connect"))
    )
    (net (code "112") (name "unconnected-(U11-NC_P7-Pad7)") (class "Default")
      (node (ref "U11") (pin "7") (pinfunction "NC_P7_7") (pintype "no_connect"))
    )
    (net (code "113") (name "unconnected-(U11-NC_P14-Pad14)") (class "Default")
      (node (ref "U11") (pin "14") (pinfunction "NC_P14_14") (pintype "no_connect"))
    )
    (net (code "114") (name "unconnected-(U12-DRDY{slash}INT2-Pad6)") (class "Default")
      (node (ref "U12") (pin "6") (pinfunction "DRDY/INT2_6") (pintype "output"))
    )
    (net (code "115") (name "unconnected-(U12-INT1-Pad7)") (class "Default")
      (node (ref "U12") (pin "7") (pinfunction "INT1_7") (pintype "output"))
    )
    (net (code "116") (name "unconnected-(U14-AUX_CL-Pad7)") (class "Default")
      (node (ref "U14") (pin "7") (pinfunction "AUX_CL_7") (pintype "bidirectional"))
    )
    (net (code "117") (name "unconnected-(U14-AUX_DA-Pad6)") (class "Default")
      (node (ref "U14") (pin "6") (pinfunction "AUX_DA_6") (pintype "bidirectional"))
    )
    (net (code "118") (name "unconnected-(U14-CLKOUT-Pad22)") (class "Default")
      (node (ref "U14") (pin "22") (pinfunction "CLKOUT_22") (pintype "bidirectional"))
    )
    (net (code "119") (name "unconnected-(U14-NC1-Pad2)") (class "Default")
      (node (ref "U14") (pin "2") (pinfunction "NC1_2") (pintype "bidirectional"))
    )
    (net (code "120") (name "unconnected-(U14-NC2-Pad3)") (class "Default")
      (node (ref "U14") (pin "3") (pinfunction "NC2_3") (pintype "bidirectional"))
    )
    (net (code "121") (name "unconnected-(U14-NC3-Pad4)") (class "Default")
      (node (ref "U14") (pin "4") (pinfunction "NC3_4") (pintype "bidirectional"))
    )
    (net (code "122") (name "unconnected-(U14-NC4-Pad5)") (class "Default")
      (node (ref "U14") (pin "5") (pinfunction "NC4_5") (pintype "bidirectional"))
    )
    (net (code "123") (name "unconnected-(U14-NC5-Pad14)") (class "Default")
      (node (ref "U14") (pin "14") (pinfunction "NC5_14") (pintype "bidirectional"))
    )
    (net (code "124") (name "unconnected-(U14-NC6-Pad15)") (class "Default")
      (node (ref "U14") (pin "15") (pinfunction "NC6_15") (pintype "bidirectional"))
    )
    (net (code "125") (name "unconnected-(U14-NC7-Pad16)") (class "Default")
      (node (ref "U14") (pin "16") (pinfunction "NC7_16") (pintype "bidirectional"))
    )
    (net (code "126") (name "unconnected-(U14-NC8-Pad17)") (class "Default")
      (node (ref "U14") (pin "17") (pinfunction "NC8_17") (pintype "bidirectional"))
    )
    (net (code "127") (name "unconnected-(U14-RESV1-Pad19)") (class "Default")
      (node (ref "U14") (pin "19") (pinfunction "RESV1_19") (pintype "bidirectional"))
    )
    (net (code "128") (name "unconnected-(U14-RESV2-Pad21)") (class "Default")
      (node (ref "U14") (pin "21") (pinfunction "RESV2_21") (pintype "bidirectional"))
    )
    (net (code "129") (name "~{JTRST}") (class "Default")
      (node (ref "!JTRST") (pin "P$1") (pinfunction "P$1_P$1") (pintype "passive"))
      (node (ref "J6") (pin "10") (pinfunction "S_10") (pintype "passive"))
      (node (ref "U1") (pin "56") (pinfunction "PB4_56") (pintype "bidirectional"))
    )
  )
)
